# DC_SPS.net
KiCad netlist of a schematic drawn in Altium Designer
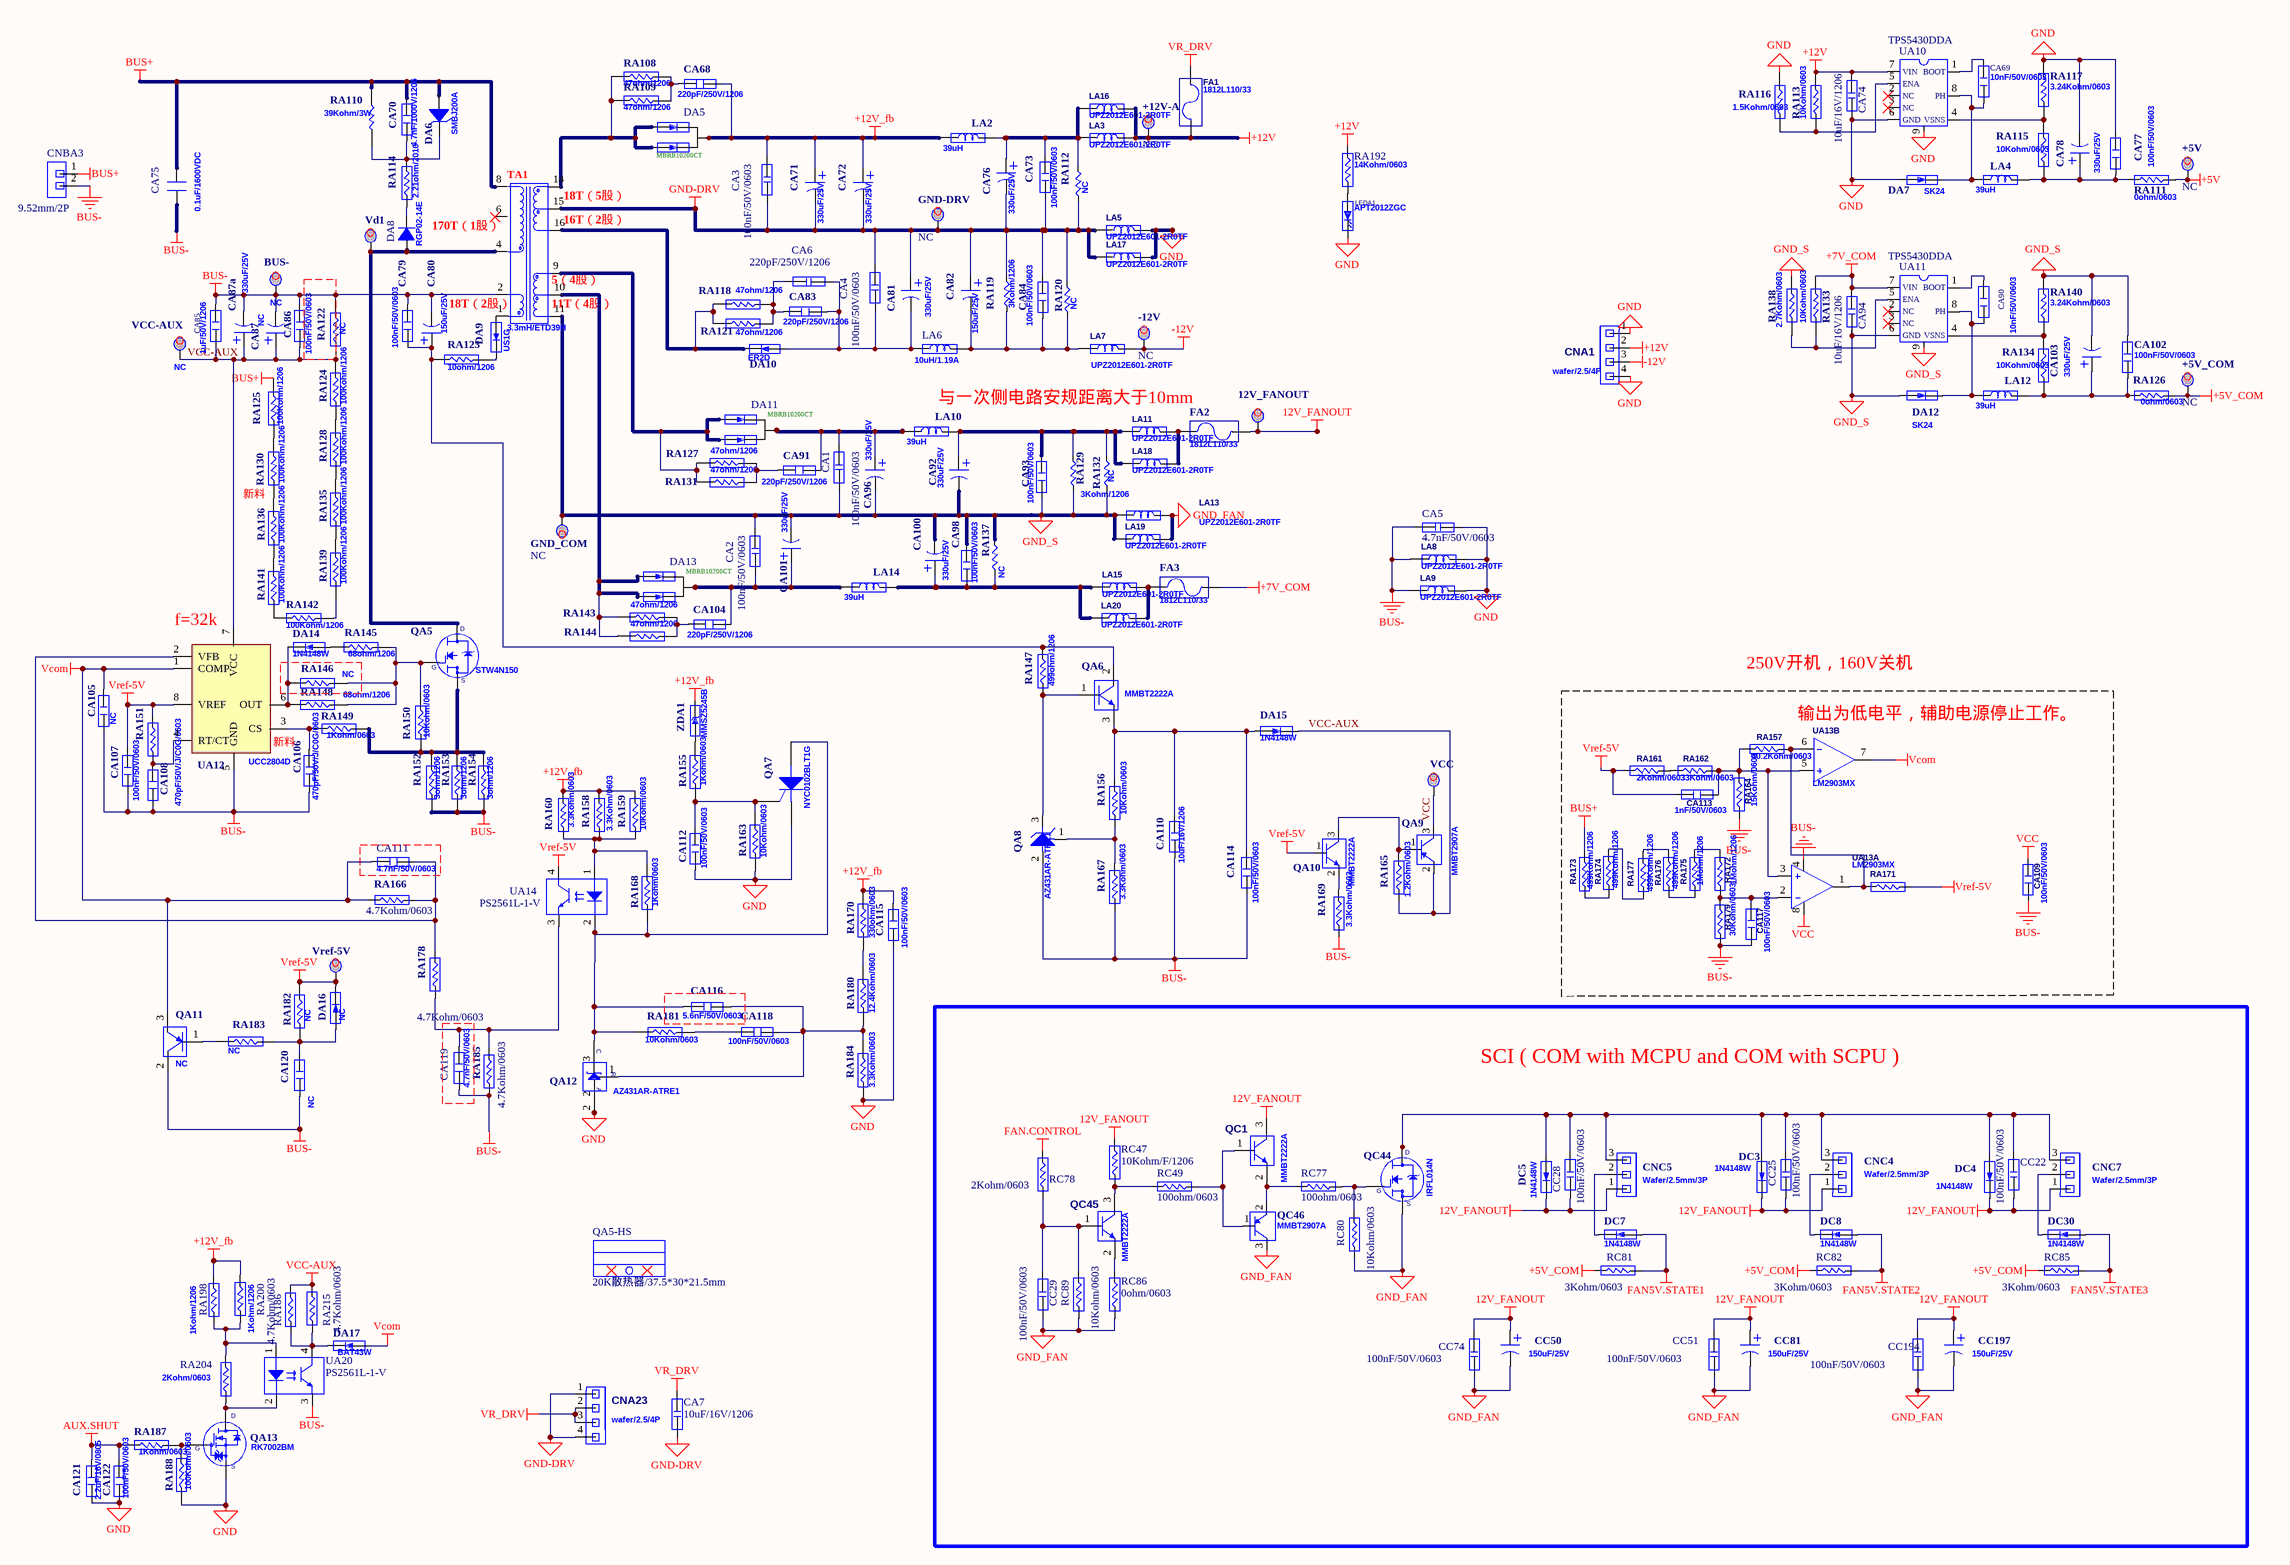
[diagram p0: DC SPS.SchDoc]

(export (version "E")
  (design (tool "Eeschema 10.0.6"))
  (components
    (comp (ref "+5V") (value "NC") (footprint "TEST-12") (libsource (lib "00") (part "17K TPD")))
    (comp (ref "+5V_COM") (value "NC") (footprint "TEST-12") (libsource (lib "00") (part "17K TPD")))
    (comp (ref "+12V-A") (value "NC") (footprint "TEST-12") (libsource (lib "00") (part "17K TPD")))
    (comp (ref "-12V") (value "NC") (footprint "TEST-12") (libsource (lib "00") (part "17K TPD")))
    (comp (ref "12V_FANOUT") (value "NC") (footprint "TEST-12") (libsource (lib "00") (part "17K TPD")))
    (comp (ref "BUS-") (value "NC") (footprint "TEST-12") (libsource (lib "00") (part "17K TPD")))
    (comp (ref "CA1")
      (value "100nF/50V/0603")
      (footprint "C0603SM")
      (description "100nF/50V/J/X7R/0603")
      (fields (field (name "Comment") "023-105220-0"))
      (libsource (lib "首航") (part "023-104320-0 C0603SM"))
    )
    (comp (ref "CA2")
      (value "100nF/50V/0603")
      (footprint "C0603SM")
      (description "100nF/50V/J/X7R/0603")
      (fields (field (name "Comment") "023-105220-0"))
      (libsource (lib "首航") (part "023-104320-0 C0603SM"))
    )
    (comp (ref "CA3")
      (value "100nF/50V/0603")
      (footprint "C0603SM")
      (description "100nF/50V/J/X7R/0603")
      (fields (field (name "Comment") "023-105220-0"))
      (libsource (lib "首航") (part "023-104320-0 C0603SM"))
    )
    (comp (ref "CA4")
      (value "100nF/50V/0603")
      (footprint "C0603SM")
      (description "100nF/50V/J/X7R/0603")
      (fields (field (name "Comment") "023-105220-0"))
      (libsource (lib "首航") (part "023-104320-0 C0603SM"))
    )
    (comp (ref "CA5")
      (value "4.7nF/50V/0603")
      (footprint "C0603SM")
      (description "4.7nF/50V/J/X7R/0603")
      (fields (field (name "Comment") "023-472220-0"))
      (libsource (lib "首航") (part "023-472220-0 C0603SM"))
    )
    (comp (ref "CA6")
      (value "220pF/250V/1206")
      (footprint "C1206SM")
      (description "220pF/250V/J/C0G/1206")
      (fields (field (name "Comment") "023-221250-0"))
      (libsource (lib "首航") (part "023-221250-0 C1206SM"))
    )
    (comp (ref "CA7")
      (value "10uF/16V/1206")
      (footprint "C1206SM")
      (description "10uF/16V/K/X7R/1206")
      (fields (field (name "Comment") "023-106350-0"))
      (libsource (lib "首航") (part "023-106350-0 C1206SM"))
    )
    (comp (ref "CA68")
      (value "220pF/250V/1206")
      (footprint "CC3216-1206")
      (description "220pF/250V/J/C0G/1206")
      (fields (field (name "Comment") "023-221250-0"))
      (libsource (lib "00") (part "C1206 SM"))
    )
    (comp (ref "CA69")
      (value "10nF/50V/0603")
      (footprint "CC1608-0603")
      (description "10nF/50V/J/X7R/0603")
      (fields (field (name "Comment") "023-103220-0"))
      (libsource (lib "CAP") (part "CC0603-103SM_J"))
    )
    (comp (ref "CA70")
      (value "4.7nF/1000V/1206")
      (footprint "CC3216-1206")
      (description "4.7nF/1000V/K/X7R/1206")
      (fields (field (name "Comment") "023-472350-0"))
      (libsource (lib "00") (part "17KC472/1KV"))
    )
    (comp (ref "CA71")
      (value "330uF/25V")
      (footprint "EC3.5/8.5")
      (description "330uF/25V/Φ8*15/4000H/EKY")
      (fields (field (name "Comment") "020-337100-0"))
      (libsource (lib "00") (part "C220UF/25V"))
    )
    (comp (ref "CA72")
      (value "330uF/25V")
      (footprint "EC3.5/8.5")
      (description "330uF/25V/Φ8*15/4000H/EKY")
      (fields (field (name "Comment") "020-337100-0"))
      (libsource (lib "00") (part "C220UF/25V"))
    )
    (comp (ref "CA73")
      (value "100nF/50V/0603")
      (footprint "CC1608-0603")
      (description "100nF/50V/J/X7R/0603")
      (fields (field (name "Comment") "023-105220-0"))
      (libsource (lib "00") (part "C0603 SM"))
    )
    (comp (ref "CA74")
      (value "10uF/16V/1206")
      (footprint "C1206SM")
      (description "10uF/16V/K/X7R/1206")
      (fields (field (name "Comment") "023-106350-0"))
      (libsource (lib "首航") (part "023-106350-0 C1206SM"))
    )
    (comp (ref "CA75")
      (value "0.1uF/1600VDC")
      (footprint "PC104/1600V-22.5")
      (description "0.1uF/1600VDC/±10%/P22.5/12*22*26.5")
      (fields (field (name "Comment") "022-104001-0"))
      (libsource (lib "CAP") (part "PC0.1uF/1600V"))
    )
    (comp (ref "CA76")
      (value "330uF/25V")
      (footprint "EC3.5/8.5")
      (description "330uF/25V/Φ8*15/4000H/EKY")
      (fields (field (name "Comment") "020-337100-0"))
      (libsource (lib "00") (part "C220UF/25V"))
    )
    (comp (ref "CA77")
      (value "100nF/50V/0603")
      (footprint "CC1608-0603")
      (description "100nF/50V/J/X7R/0603")
      (fields (field (name "Comment") "023-105220-0"))
      (libsource (lib "00") (part "C0603 SM"))
    )
    (comp (ref "CA78")
      (value "330uF/25V")
      (footprint "EC3.5/8.5")
      (description "330uF/25V/Φ8*15/4000H/EKY")
      (fields (field (name "Comment") "020-337100-0"))
      (libsource (lib "00") (part "C220UF/25V"))
    )
    (comp (ref "CA79")
      (value "100nF/50V/0603")
      (footprint "CC1608-0603")
      (description "100nF/50V/J/X7R/0603")
      (fields (field (name "Comment") "023-105220-0"))
      (libsource (lib "00") (part "C0603 SM"))
    )
    (comp (ref "CA80")
      (value "150uF/25V")
      (footprint "EC2.54/6.3")
      (description "150uF/25V/P2.5/Φ6.3*11/6000H")
      (fields (field (name "Comment") "020-157111-0"))
      (libsource (lib "00") (part "C100UF插件"))
    )
    (comp (ref "CA81")
      (value "330uF/25V")
      (footprint "EC3.5/8.5")
      (description "330uF/25V/Φ8*15/4000H/EKY")
      (fields (field (name "Comment") "020-337100-0"))
      (libsource (lib "00") (part "C220UF/25V"))
    )
    (comp (ref "CA82")
      (value "150uF/25V")
      (footprint "EC2.54/6.3")
      (description "150uF/25V/P2.5/Φ6.3*11/6000H")
      (fields (field (name "Comment") "020-157111-0"))
      (libsource (lib "00") (part "C100UF插件"))
    )
    (comp (ref "CA83")
      (value "220pF/250V/1206")
      (footprint "CC3216-1206")
      (description "220pF/250V/J/C0G/1206")
      (fields (field (name "Comment") "023-221250-0"))
      (libsource (lib "00") (part "C1206 SM"))
    )
    (comp (ref "CA84")
      (value "100nF/50V/0603")
      (footprint "CC1608-0603")
      (description "100nF/50V/J/X7R/0603")
      (fields (field (name "Comment") "023-105220-0"))
      (libsource (lib "00") (part "C0603 SM"))
    )
    (comp (ref "CA85")
      (value "1uF/50V/1206")
      (footprint "CC3216-1206")
      (description "1uF/50V/K/X7R/1206")
      (fields (field (name "Comment") "023-105250-0"))
      (libsource (lib "00") (part "C1206 SM"))
    )
    (comp (ref "CA86")
      (value "100nF/50V/0603")
      (footprint "CC1608-0603")
      (description "100nF/50V/J/X7R/0603")
      (fields (field (name "Comment") "023-105220-0"))
      (libsource (lib "00") (part "C0603 SM"))
    )
    (comp (ref "CA87") (value "NC") (footprint "EC2.54/6.3") (libsource (lib "00") (part "C100UF插件")))
    (comp (ref "CA87a")
      (value "330uF/25V")
      (footprint "EC3.5/8.5")
      (description "330uF/25V/Φ8*15/4000H/EKY")
      (fields (field (name "Comment") "020-337100-0"))
      (libsource (lib "00") (part "C220UF/25V"))
    )
    (comp (ref "CA90")
      (value "10nF/50V/0603")
      (footprint "CC1608-0603")
      (description "10nF/50V/J/X7R/0603")
      (fields (field (name "Comment") "023-103220-0"))
      (libsource (lib "CAP") (part "CC0603-103SM_J"))
    )
    (comp (ref "CA91")
      (value "220pF/250V/1206")
      (footprint "CC3216-1206")
      (description "220pF/250V/J/C0G/1206")
      (fields (field (name "Comment") "023-221250-0"))
      (libsource (lib "00") (part "C1206 SM"))
    )
    (comp (ref "CA92")
      (value "330uF/25V")
      (footprint "EC3.5/8.5")
      (description "330uF/25V/Φ8*15/4000H/EKY")
      (fields (field (name "Comment") "020-337100-0"))
      (libsource (lib "00") (part "C220UF/25V"))
    )
    (comp (ref "CA93")
      (value "100nF/50V/0603")
      (footprint "CC1608-0603")
      (description "100nF/50V/J/X7R/0603")
      (fields (field (name "Comment") "023-105220-0"))
      (libsource (lib "00") (part "C0603 SM"))
    )
    (comp (ref "CA94")
      (value "10uF/16V/1206")
      (footprint "C1206SM")
      (description "10uF/16V/K/X7R/1206")
      (fields (field (name "Comment") "023-106350-0"))
      (libsource (lib "首航") (part "023-106350-0 C1206SM"))
    )
    (comp (ref "CA96")
      (value "330uF/25V")
      (footprint "EC3.5/8.5")
      (description "330uF/25V/Φ8*15/4000H/EKY")
      (fields (field (name "Comment") "020-337100-0"))
      (libsource (lib "00") (part "C220UF/25V"))
    )
    (comp (ref "CA98")
      (value "100nF/50V/0603")
      (footprint "CC1608-0603")
      (description "100nF/50V/J/X7R/0603")
      (fields (field (name "Comment") "023-105220-0"))
      (libsource (lib "00") (part "C0603 SM"))
    )
    (comp (ref "CA100")
      (value "330uF/25V")
      (footprint "EC3.5/8.5")
      (description "330uF/25V/Φ8*15/4000H/EKY")
      (fields (field (name "Comment") "020-337100-0"))
      (libsource (lib "00") (part "C220UF/25V"))
    )
    (comp (ref "CA101")
      (value "330uF/25V")
      (footprint "EC3.5/8.5")
      (description "330uF/25V/Φ8*15/4000H/EKY")
      (fields (field (name "Comment") "020-337100-0"))
      (libsource (lib "00") (part "C220UF/25V"))
    )
    (comp (ref "CA102")
      (value "100nF/50V/0603")
      (footprint "CC1608-0603")
      (description "100nF/50V/J/X7R/0603")
      (fields (field (name "Comment") "023-105220-0"))
      (libsource (lib "00") (part "C0603 SM"))
    )
    (comp (ref "CA103")
      (value "330uF/25V")
      (footprint "EC3.5/8.5")
      (description "330uF/25V/Φ8*15/4000H/EKY")
      (fields (field (name "Comment") "020-337100-0"))
      (libsource (lib "00") (part "C220UF/25V"))
    )
    (comp (ref "CA104")
      (value "220pF/250V/1206")
      (footprint "CC3216-1206")
      (description "220pF/250V/J/C0G/1206")
      (fields (field (name "Comment") "023-221250-0"))
      (libsource (lib "00") (part "C1206 SM"))
    )
    (comp (ref "CA105") (value "NC") (footprint "CC1608-0603") (libsource (lib "00") (part "C0603 SM")))
    (comp (ref "CA106")
      (value "470pF/50V/J/C0G/0603")
      (footprint "CC1608-0603")
      (fields (field (name "Comment") "023-471220-0"))
      (libsource (lib "00") (part "C0603 SM"))
    )
    (comp (ref "CA107")
      (value "100nF/50V/0603")
      (footprint "CC1608-0603")
      (description "100nF/50V/J/X7R/0603")
      (fields (field (name "Comment") "023-105220-0"))
      (libsource (lib "") (part "C0603 SM_1"))
    )
    (comp (ref "CA108")
      (value "470pF/50V/J/C0G/0603")
      (footprint "CC1608-0603")
      (fields (field (name "Comment") "023-471220-0"))
      (libsource (lib "CAP") (part "CC0603-471SM"))
    )
    (comp (ref "CA109")
      (value "100nF/50V/0603")
      (footprint "CC1608-0603")
      (description "100nF/50V/J/X7R/0603")
      (fields (field (name "Comment") "023-105220-0"))
      (libsource (lib "CAP") (part "CC0603-104SM_J"))
    )
    (comp (ref "CA110")
      (value "10uF/16V/1206")
      (footprint "CC3216-1206")
      (description "10uF/16V/K/X7R/1206")
      (fields (field (name "Comment") "023-106350-0"))
      (libsource (lib "CAP") (part "CC1206-106/16VSM"))
    )
    (comp (ref "CA111")
      (value "4.7nF/50V/0603")
      (footprint "CC1608-0603")
      (description "4.7nF/50V/J/X7R/0603")
      (fields (field (name "Comment") "023-472220-0"))
      (libsource (lib "CAP") (part "CC0603-103SM"))
    )
    (comp (ref "CA112")
      (value "100nF/50V/0603")
      (footprint "CC1608-0603")
      (description "100nF/50V/J/X7R/0603")
      (fields (field (name "Comment") "023-105220-0"))
      (libsource (lib "00") (part "C0603 SM"))
    )
    (comp (ref "CA113")
      (value "1nF/50V/0603")
      (footprint "CC1608-0603")
      (description "1nF/50V/J/C0G/0603")
      (fields (field (name "Comment") "023-102220-0"))
      (libsource (lib "CAP") (part "CC0603-102SM"))
    )
    (comp (ref "CA114")
      (value "100nF/50V/0603")
      (footprint "CC1608-0603")
      (description "100nF/50V/J/X7R/0603")
      (fields (field (name "Comment") "023-105220-0"))
      (libsource (lib "00") (part "C0603 SM"))
    )
    (comp (ref "CA115")
      (value "100nF/50V/0603")
      (footprint "CC1608-0603")
      (description "100nF/50V/J/X7R/0603")
      (fields (field (name "Comment") "023-105220-0"))
      (libsource (lib "00") (part "C0603 SM"))
    )
    (comp (ref "CA116")
      (value "5.6nF/50V/0603")
      (footprint "CC1608-0603")
      (description "5.6nF/50V/K/0603")
      (fields (field (name "Comment") "023-562220-0"))
      (libsource (lib "") (part "C0603 SM_1"))
    )
    (comp (ref "CA117")
      (value "100nF/50V/0603")
      (footprint "CC1608-0603")
      (description "100nF/50V/J/X7R/0603")
      (fields (field (name "Comment") "023-105220-0"))
      (libsource (lib "CAP") (part "CC0603-104SM_J"))
    )
    (comp (ref "CA118")
      (value "100nF/50V/0603")
      (footprint "CC1608-0603")
      (description "100nF/50V/J/X7R/0603")
      (fields (field (name "Comment") "023-105220-0"))
      (libsource (lib "00") (part "C0603 SM"))
    )
    (comp (ref "CA119")
      (value "4.7nF/50V/0603")
      (footprint "CC1608-0603")
      (description "4.7nF/50V/J/X7R/0603")
      (fields (field (name "Comment") "023-472220-0"))
      (libsource (lib "CAP") (part "CC0603-103SM"))
    )
    (comp (ref "CA120") (value "NC") (footprint "CC1608-0603") (libsource (lib "00") (part "C0603 SM")))
    (comp (ref "CA121")
      (value "2.2uF/16V/0805")
      (footprint "CC2012-0805")
      (description "2.2uF/16V/K/X7R/0805")
      (fields (field (name "Comment") "023-225330-0"))
      (libsource (lib "CAP") (part "CC0805-225/16VSM"))
    )
    (comp (ref "CA122")
      (value "100nF/50V/0603")
      (footprint "CC1608-0603")
      (description "100nF/50V/J/X7R/0603")
      (fields (field (name "Comment") "023-105220-0"))
      (libsource (lib "00") (part "C0603 SM"))
    )
    (comp (ref "CC22")
      (value "100nF/50V/0603")
      (footprint "C0603SM")
      (description "100nF/50V/J/X7R/0603")
      (fields (field (name "Comment") "023-105220-0"))
      (libsource (lib "首航") (part "023-104320-0 C0603SM"))
    )
    (comp (ref "CC25")
      (value "100nF/50V/0603")
      (footprint "C0603SM")
      (description "100nF/50V/J/X7R/0603")
      (fields (field (name "Comment") "023-105220-0"))
      (libsource (lib "首航") (part "023-104320-0 C0603SM"))
    )
    (comp (ref "CC28")
      (value "100nF/50V/0603")
      (footprint "C0603SM")
      (description "100nF/50V/J/X7R/0603")
      (fields (field (name "Comment") "023-105220-0"))
      (libsource (lib "首航") (part "023-104320-0 C0603SM"))
    )
    (comp (ref "CC29")
      (value "100nF/50V/0603")
      (footprint "C0603SM")
      (description "100nF/50V/J/X7R/0603")
      (fields (field (name "Comment") "023-105220-0"))
      (libsource (lib "首航") (part "023-104320-0 C0603SM"))
    )
    (comp (ref "CC50")
      (value "150uF/25V")
      (footprint "EC2.54/6.3")
      (description "150uF/25V/P2.5/Φ6.3*11/6000H")
      (fields (field (name "Comment") "020-157111-0"))
      (libsource (lib "00") (part "C100UF插件"))
    )
    (comp (ref "CC51")
      (value "100nF/50V/0603")
      (footprint "C0603SM")
      (description "100nF/50V/J/X7R/0603")
      (fields (field (name "Comment") "023-105220-0"))
      (libsource (lib "首航") (part "023-104320-0 C0603SM"))
    )
    (comp (ref "CC74")
      (value "100nF/50V/0603")
      (footprint "C0603SM")
      (description "100nF/50V/J/X7R/0603")
      (fields (field (name "Comment") "023-105220-0"))
      (libsource (lib "首航") (part "023-104320-0 C0603SM"))
    )
    (comp (ref "CC81")
      (value "150uF/25V")
      (footprint "EC2.54/6.3")
      (description "150uF/25V/P2.5/Φ6.3*11/6000H")
      (fields (field (name "Comment") "020-157111-0"))
      (libsource (lib "00") (part "C100UF插件"))
    )
    (comp (ref "CC194")
      (value "100nF/50V/0603")
      (footprint "C0603SM")
      (description "100nF/50V/J/X7R/0603")
      (fields (field (name "Comment") "023-105220-0"))
      (libsource (lib "首航") (part "023-104320-0 C0603SM"))
    )
    (comp (ref "CC197")
      (value "150uF/25V")
      (footprint "EC2.54/6.3")
      (description "150uF/25V/P2.5/Φ6.3*11/6000H")
      (fields (field (name "Comment") "020-157111-0"))
      (libsource (lib "00") (part "C100UF插件"))
    )
    (comp (ref "CNA1")
      (value "wafer/2.5/4P")
      (footprint "CN2.5-4P")
      (description "Wafer/2.5 pitch/4 pin/182度/白胶/带卡勾")
      (fields (field (name "Comment") "110-252000-0"))
      (libsource (lib "00") (part "CN 25P04"))
    )
    (comp (ref "CNA23")
      (value "wafer/2.5/4P")
      (footprint "CN2.5-4P")
      (description "Wafer/2.5 pitch/4 pin/182度/白胶/带卡勾")
      (fields (field (name "Comment") "110-252000-0"))
      (libsource (lib "00") (part "CN 25P04"))
    )
    (comp (ref "CNBA3")
      (value "9.52mm/2P")
      (footprint "CN2P9.52")
      (description "接线端子台/9.52mm/2P")
      (fields (field (name "Comment") "110-309501-0"))
      (libsource (lib "zcp") (part "110-309500-0 CN2P9.52"))
    )
    (comp (ref "CNC4")
      (value "Wafer/2.5mm/3P")
      (footprint "CN2.5-3P")
      (description "Wafer/2.5 pitch/3 pin/181度/白胶/带卡勾")
      (fields (field (name "Comment") "110-251000-0"))
      (libsource (lib "00") (part "CN 25P03"))
    )
    (comp (ref "CNC5")
      (value "Wafer/2.5mm/3P")
      (footprint "CN2.5-3P")
      (description "Wafer/2.5 pitch/3 pin/181度/白胶/带卡勾")
      (fields (field (name "Comment") "110-251000-0"))
      (libsource (lib "00") (part "CN 25P03"))
    )
    (comp (ref "CNC7")
      (value "Wafer/2.5mm/3P")
      (footprint "CN2.5-3P")
      (description "Wafer/2.5 pitch/3 pin/181度/白胶/带卡勾")
      (fields (field (name "Comment") "110-251000-0"))
      (libsource (lib "00") (part "CN 25P03"))
    )
    (comp (ref "DA5")
      (value "MBRB10200CT")
      (footprint "D2PAK - 1")
      (description "10A/200V/D(2)PAK")
      (fields (field (name "Comment") "060-310030-0"))
      (libsource (lib "samilpower_Library-01") (part "D MBRB10200CT"))
    )
    (comp (ref "DA6")
      (value "SMBJ200A")
      (footprint "TVS-SMB")
      (description "200V/600W/DO-214AA")
      (fields (field (name "Comment") "083-100010-0"))
      (libsource (lib "00") (part "17KP6SMBJ170"))
    )
    (comp (ref "DA7")
      (value "SK24")
      (footprint "DO-SMB")
      (description "2A/40V/DO-214AA")
      (fields (field (name "Comment") "060-310020-0"))
      (libsource (lib "00") (part "D SK24"))
    )
    (comp (ref "DA8")
      (value "RGP02-14E")
      (footprint "DO-5.08/2.5")
      (description "0.5A/1400V/DO-41")
      (fields (field (name "Comment") "060-100000-0"))
      (libsource (lib "zhu-lib") (part "D RGP02-14E"))
    )
    (comp (ref "DA9")
      (value "US1G")
      (footprint "DO-SMA")
      (description "1A/400V/DO-214AC")
      (fields (field (name "Comment") "060-110010-0"))
      (libsource (lib "00") (part "17KUS1G"))
    )
    (comp (ref "DA10")
      (value "ER2D")
      (footprint "DO-SMA")
      (description "2A/200V/SMB")
      (fields (field (name "Comment") "060-110000-0"))
      (libsource (lib "00") (part "D MURA220T3"))
    )
    (comp (ref "DA11")
      (value "MBRB10200CT")
      (footprint "D2PAK - 1")
      (description "10A/200V/D(2)PAK")
      (fields (field (name "Comment") "060-310030-0"))
      (libsource (lib "samilpower_Library-01") (part "D MBRB10200CT"))
    )
    (comp (ref "DA12")
      (value "SK24")
      (footprint "DO-SMB")
      (description "2A/40V/DO-214AA")
      (fields (field (name "Comment") "060-310020-0"))
      (libsource (lib "00") (part "D SK24"))
    )
    (comp (ref "DA13")
      (value "MBRB10200CT")
      (footprint "D2PAK - 1")
      (description "10A/200V/D(2)PAK")
      (fields (field (name "Comment") "060-310030-0"))
      (libsource (lib "samilpower_Library-01") (part "D MBRB10200CT"))
    )
    (comp (ref "DA14")
      (value "1N4148W")
      (footprint "SOD-123")
      (description "0.15A/75V/SOD-123")
      (fields (field (name "Comment") "060-500010-0"))
      (libsource (lib "00") (part "D 1N4148W"))
    )
    (comp (ref "DA15")
      (value "1N4148W")
      (footprint "SOD-123")
      (description "0.15A/75V/SOD-123")
      (fields (field (name "Comment") "060-500010-0"))
      (libsource (lib "00") (part "D 1N4148W"))
    )
    (comp (ref "DA16") (value "NC") (footprint "SOD-123") (libsource (lib "00") (part "D 1N4148W")))
    (comp (ref "DA17")
      (value "BAT43W")
      (footprint "SOD-123")
      (description "0.2A/30V/SOD-123")
      (fields (field (name "Comment") "060-310000-0"))
      (libsource (lib "00") (part "D S123SM"))
    )
    (comp (ref "DC3")
      (value "1N4148W")
      (footprint "SOD-123")
      (description "0.15A/75V/SOD-123")
      (fields (field (name "Comment") "060-500010-0"))
      (libsource (lib "00") (part "D 1N4148W"))
    )
    (comp (ref "DC4")
      (value "1N4148W")
      (footprint "SOD-123")
      (description "0.15A/75V/SOD-123")
      (fields (field (name "Comment") "060-500010-0"))
      (libsource (lib "00") (part "D 1N4148W"))
    )
    (comp (ref "DC5")
      (value "1N4148W")
      (footprint "SOD-123")
      (description "0.15A/75V/SOD-123")
      (fields (field (name "Comment") "060-500010-0"))
      (libsource (lib "00") (part "D 1N4148W"))
    )
    (comp (ref "DC7")
      (value "1N4148W")
      (footprint "SOD-123")
      (description "0.15A/75V/SOD-123")
      (fields (field (name "Comment") "060-500010-0"))
      (libsource (lib "00") (part "D 1N4148W"))
    )
    (comp (ref "DC8")
      (value "1N4148W")
      (footprint "SOD-123")
      (description "0.15A/75V/SOD-123")
      (fields (field (name "Comment") "060-500010-0"))
      (libsource (lib "00") (part "D 1N4148W"))
    )
    (comp (ref "DC30")
      (value "1N4148W")
      (footprint "SOD-123")
      (description "0.15A/75V/SOD-123")
      (fields (field (name "Comment") "060-500010-0"))
      (libsource (lib "00") (part "D 1N4148W"))
    )
    (comp (ref "FA1")
      (value "1812L110/33")
      (footprint "17KFUSE1812L110-33")
      (description "1812L Series/1.1A/33V")
      (fields (field (name "Comment") "160-201000-0"))
      (libsource (lib "01") (part "FS 1812L110-33MR"))
    )
    (comp (ref "FA2")
      (value "1812L110/33")
      (footprint "17KFUSE1812L110-33")
      (description "1812L Series/1.1A/33V")
      (fields (field (name "Comment") "160-201000-0"))
      (libsource (lib "00") (part "17KFUSE1812L110-33"))
    )
    (comp (ref "FA3")
      (value "1812L110/33")
      (footprint "17KFUSE1812L110-33")
      (description "1812L Series/1.1A/33V")
      (fields (field (name "Comment") "160-201000-0"))
      (libsource (lib "00") (part "17KFUSE1812L110-33"))
    )
    (comp (ref "GND-DRV") (value "NC") (footprint "TEST-12") (libsource (lib "00") (part "17K TPD")))
    (comp (ref "GND_COM") (value "NC") (footprint "TEST-12") (libsource (lib "00") (part "17K TPD")))
    (comp (ref "LA2")
      (value "39uH")
      (footprint "L1110SM- 39UH")
      (description "39uH/DR10*5.4RB K38/RI10*3.4*8.2 K38")
      (fields (field (name "Comment") "040-390000-0"))
      (libsource (lib "00") (part "L10090SM"))
    )
    (comp (ref "LA3")
      (value "UPZ2012E601-2R0TF")
      (footprint "L2012-0805")
      (description "600ohm/2A/100MHz/0805")
      (fields (field (name "Comment") "080-200000-0"))
      (libsource (lib "linshi") (part "L-UPZ2012E601-2R0TF"))
    )
    (comp (ref "LA4")
      (value "39uH")
      (footprint "L1110SM- 39UH")
      (description "39uH/DR10*5.4RB K38/RI10*3.4*8.2 K38")
      (fields (field (name "Comment") "040-390000-0"))
      (libsource (lib "00") (part "L10090SM"))
    )
    (comp (ref "LA5")
      (value "UPZ2012E601-2R0TF")
      (footprint "L2012-0805")
      (description "600ohm/2A/100MHz/0805")
      (fields (field (name "Comment") "080-200000-0"))
      (libsource (lib "linshi") (part "L-UPZ2012E601-2R0TF"))
    )
    (comp (ref "LA6")
      (value "10uH/1.19A")
      (footprint "L4848SM")
      (description "10uH/1.19A/±30%/4.8*4.8*2.8mm")
      (fields (field (name "Comment") "040-109100-0"))
      (libsource (lib "00") (part "L7444043100SM"))
    )
    (comp (ref "LA7")
      (value "UPZ2012E601-2R0TF")
      (footprint "L2012-0805")
      (description "600ohm/2A/100MHz/0805")
      (fields (field (name "Comment") "080-200000-0"))
      (libsource (lib "linshi") (part "L-UPZ2012E601-2R0TF"))
    )
    (comp (ref "LA8")
      (value "UPZ2012E601-2R0TF")
      (footprint "L2012-0805")
      (description "600ohm/2A/100MHz/0805")
      (fields (field (name "Comment") "080-200000-0"))
      (libsource (lib "linshi") (part "L-UPZ2012E601-2R0TF"))
    )
    (comp (ref "LA9")
      (value "UPZ2012E601-2R0TF")
      (footprint "L2012-0805")
      (description "600ohm/2A/100MHz/0805")
      (fields (field (name "Comment") "080-200000-0"))
      (libsource (lib "linshi") (part "L-UPZ2012E601-2R0TF"))
    )
    (comp (ref "LA10")
      (value "39uH")
      (footprint "L1110SM- 39UH")
      (description "39uH/DR10*5.4RB K38/RI10*3.4*8.2 K38")
      (fields (field (name "Comment") "040-390000-0"))
      (libsource (lib "00") (part "L10090SM"))
    )
    (comp (ref "LA11")
      (value "UPZ2012E601-2R0TF")
      (footprint "L2012-0805")
      (description "600ohm/2A/100MHz/0805")
      (fields (field (name "Comment") "080-200000-0"))
      (libsource (lib "linshi") (part "L-UPZ2012E601-2R0TF"))
    )
    (comp (ref "LA12")
      (value "39uH")
      (footprint "L1110SM- 39UH")
      (description "39uH/DR10*5.4RB K38/RI10*3.4*8.2 K38")
      (fields (field (name "Comment") "040-390000-0"))
      (libsource (lib "00") (part "L10090SM"))
    )
    (comp (ref "LA13")
      (value "UPZ2012E601-2R0TF")
      (footprint "L2012-0805")
      (description "600ohm/2A/100MHz/0805")
      (fields (field (name "Comment") "080-200000-0"))
      (libsource (lib "linshi") (part "L-UPZ2012E601-2R0TF"))
    )
    (comp (ref "LA14")
      (value "39uH")
      (footprint "L1110SM- 39UH")
      (description "39uH/DR10*5.4RB K38/RI10*3.4*8.2 K38")
      (fields (field (name "Comment") "040-390000-0"))
      (libsource (lib "00") (part "L10090SM"))
    )
    (comp (ref "LA15")
      (value "UPZ2012E601-2R0TF")
      (footprint "L2012-0805")
      (description "600ohm/2A/100MHz/0805")
      (fields (field (name "Comment") "080-200000-0"))
      (libsource (lib "linshi") (part "L-UPZ2012E601-2R0TF"))
    )
    (comp (ref "LA16")
      (value "UPZ2012E601-2R0TF")
      (footprint "L2012-0805")
      (description "600ohm/2A/100MHz/0805")
      (fields (field (name "Comment") "080-200000-0"))
      (libsource (lib "linshi") (part "L-UPZ2012E601-2R0TF"))
    )
    (comp (ref "LA17")
      (value "UPZ2012E601-2R0TF")
      (footprint "L2012-0805")
      (description "600ohm/2A/100MHz/0805")
      (fields (field (name "Comment") "080-200000-0"))
      (libsource (lib "linshi") (part "L-UPZ2012E601-2R0TF"))
    )
    (comp (ref "LA18")
      (value "UPZ2012E601-2R0TF")
      (footprint "L2012-0805")
      (description "600ohm/2A/100MHz/0805")
      (fields (field (name "Comment") "080-200000-0"))
      (libsource (lib "linshi") (part "L-UPZ2012E601-2R0TF"))
    )
    (comp (ref "LA19")
      (value "UPZ2012E601-2R0TF")
      (footprint "L2012-0805")
      (description "600ohm/2A/100MHz/0805")
      (fields (field (name "Comment") "080-200000-0"))
      (libsource (lib "linshi") (part "L-UPZ2012E601-2R0TF"))
    )
    (comp (ref "LA20")
      (value "UPZ2012E601-2R0TF")
      (footprint "L2012-0805")
      (description "600ohm/2A/100MHz/0805")
      (fields (field (name "Comment") "080-200000-0"))
      (libsource (lib "linshi") (part "L-UPZ2012E601-2R0TF"))
    )
    (comp (ref "LEDA1")
      (value "APT2012ZGC")
      (footprint "LED2012-0805SM")
      (description "2.0*1.25*0.75mm/Green")
      (fields (field (name "Comment") "060-011000-0"))
      (libsource (lib "zhu-lib") (part "D LED0805_Green"))
    )
    (comp (ref "QA5")
      (value "STW4N150")
      (footprint "TO-247")
      (description "4A/1500V/TO-247")
      (fields (field (name "Comment") "063-000010-0"))
      (libsource (lib "00") (part "17KIRF740"))
    )
    (comp (ref "QA5-HS")
      (value "20K散热器/37.5*30*21.5mm")
      (footprint "HS30x10x37.5")
      (fields (field (name "Comment") "431-100000-0"))
      (libsource (lib "zcp") (part "431-100000-0 HS30x10x37.5"))
    )
    (comp (ref "QA6")
      (value "MMBT2222A")
      (footprint "SOT-23")
      (description "0.6A/40VDC/SOT-23")
      (fields (field (name "Comment") "061-010000-0"))
      (libsource (lib "01") (part "TR 2SC4672SM"))
    )
    (comp (ref "QA7")
      (value "NYC0102BLT1G")
      (footprint "SOT-23")
      (description "0.25A/200V/SOT-23")
      (fields (field (name "Comment") "062-000010-0"))
      (libsource (lib "Miscellaneous Devices") (part "SCR"))
    )
    (comp (ref "QA8")
      (value "AZ431AR-ATRE1")
      (footprint "SOT89N")
      (description "Shunt Regulators/SOT-89")
      (fields (field (name "Comment") "050-210020-0"))
      (libsource (lib "01") (part "IC TL431SM"))
    )
    (comp (ref "QA9")
      (value "MMBT2907A")
      (footprint "SOT-23")
      (description "0.6A/60VDC/SOT-23")
      (fields (field (name "Comment") "061-110000-0"))
      (libsource (lib "01") (part "TR 2907SM"))
    )
    (comp (ref "QA10")
      (value "MMBT2222A")
      (footprint "SOT-23")
      (description "0.6A/40VDC/SOT-23")
      (fields (field (name "Comment") "061-010000-0"))
      (libsource (lib "01") (part "TR 2222SM"))
    )
    (comp (ref "QA11") (value "NC") (footprint "SOT-23") (libsource (lib "01") (part "TR 2SA1213SM")))
    (comp (ref "QA12")
      (value "AZ431AR-ATRE1")
      (footprint "SOT89N")
      (description "Shunt Regulators/SOT-89")
      (fields (field (name "Comment") "050-210020-0"))
      (libsource (lib "00") (part "IC 431SM"))
    )
    (comp (ref "QA13")
      (value "RK7002BM")
      (footprint "SOT-23 - 1")
      (description "250mA/60V/SOT-23")
      (fields (field (name "Comment") "063-010010-0"))
      (libsource (lib "samilpower_Library-01") (part "MOS RK7002SM"))
    )
    (comp (ref "QC1")
      (value "MMBT2222A")
      (footprint "SOT-23")
      (description "0.6A/40VDC/SOT-23")
      (fields (field (name "Comment") "061-010000-0"))
      (libsource (lib "samilpower_Library-01") (part "TR 2222SM"))
    )
    (comp (ref "QC44")
      (value "IRFL014N")
      (footprint "SOT223")
      (description "1.9A/55V/SOT-223")
      (fields (field (name "Comment") "063-010000-0"))
      (libsource (lib "00") (part "17KIRFL014NTRPBF"))
    )
    (comp (ref "QC45")
      (value "MMBT2222A")
      (footprint "SOT-23")
      (description "0.6A/40VDC/SOT-23")
      (fields (field (name "Comment") "061-010000-0"))
      (libsource (lib "samilpower_Library-01") (part "TR 2222SM"))
    )
    (comp (ref "QC46")
      (value "MMBT2907A")
      (footprint "SOT-23")
      (description "0.6A/60VDC/SOT-23")
      (fields (field (name "Comment") "061-110000-0"))
      (libsource (lib "01") (part "TR 2907SM"))
    )
    (comp (ref "RA108")
      (value "47ohm/1206")
      (footprint "R3216-1206")
      (description "47ohm/1/4W/F/1206")
      (fields (field (name "Comment") "011-470050-0"))
      (libsource (lib "00") (part "R1206SM"))
    )
    (comp (ref "RA109")
      (value "47ohm/1206")
      (footprint "R3216-1206")
      (description "47ohm/1/4W/F/1206")
      (fields (field (name "Comment") "011-470050-0"))
      (libsource (lib "00") (part "R1206SM"))
    )
    (comp (ref "RA110")
      (value "39Kohm/3W")
      (footprint "R3WA-5.0-S")
      (description "39Kohm/3W/J/15.5*5")
      (fields (field (name "Comment") "013-390240-0"))
      (libsource (lib "ZHU") (part "RSS 3W 39K"))
    )
    (comp (ref "RA111")
      (value "0ohm/0603")
      (footprint "R1608-0603")
      (description "0ohm/1/10W/F/0603")
      (fields (field (name "Comment") "011-000020-0"))
      (libsource (lib "RES") (part "R0603SM-3K3"))
    )
    (comp (ref "RA112") (value "NC") (footprint "R3216-1206") (libsource (lib "RES") (part "R3W-7K5")))
    (comp (ref "RA113")
      (value "10Kohm/0603")
      (footprint "R1608-0603")
      (description "10Kohm/1/10W/F/0603")
      (fields (field (name "Comment") "011-103020-0"))
      (libsource (lib "00") (part "R0603SM"))
    )
    (comp (ref "RA114")
      (value "2.21ohm/2010")
      (footprint "R5025-2010")
      (description "2.21ohm/1/2W/F/2010")
      (fields (field (name "Comment") "011-227070-0"))
      (libsource (lib "RES") (part "R2010SM-221R"))
    )
    (comp (ref "RA115")
      (value "10Kohm/0603")
      (footprint "R1608-0603")
      (description "10Kohm/1/10W/F/0603")
      (fields (field (name "Comment") "011-103020-0"))
      (libsource (lib "00") (part "R0603SM"))
    )
    (comp (ref "RA116")
      (value "1.5Kohm/0603")
      (footprint "R1608-0603")
      (description "1.5Kohm/1/10W/F/0603")
      (fields (field (name "Comment") "011-152020-0"))
      (libsource (lib "00") (part "R0603SM"))
    )
    (comp (ref "RA117")
      (value "3.24Kohm/0603")
      (footprint "R1608-0603")
      (description "3.24Kohm/1/10W/F/0603")
      (fields (field (name "Comment") "011-322020-0"))
      (libsource (lib "00") (part "R0603SM"))
    )
    (comp (ref "RA118")
      (value "47ohm/1206")
      (footprint "R3216-1206")
      (description "47ohm/1/4W/F/1206")
      (fields (field (name "Comment") "011-470050-0"))
      (libsource (lib "00") (part "R1206SM"))
    )
    (comp (ref "RA119")
      (value "3Kohm/1206")
      (footprint "R3216-1206")
      (description "3Kohm/1/4W/F/1206")
      (fields (field (name "Comment") "011-302050-0"))
      (libsource (lib "RES") (part "R3W-7K5"))
    )
    (comp (ref "RA120") (value "NC") (footprint "R3216-1206") (libsource (lib "RES") (part "R3W-7K5")))
    (comp (ref "RA121")
      (value "47ohm/1206")
      (footprint "R3216-1206")
      (description "47ohm/1/4W/F/1206")
      (fields (field (name "Comment") "011-470050-0"))
      (libsource (lib "00") (part "R1206SM"))
    )
    (comp (ref "RA122") (value "NC") (footprint "R1608-0603") (libsource (lib "00") (part "R0603SM")))
    (comp (ref "RA123")
      (value "10ohm/1206")
      (footprint "R3216-1206")
      (description "10ohm/1/4W/F/1206")
      (fields (field (name "Comment") "011-100050-0"))
      (libsource (lib "00") (part "R1206SM"))
    )
    (comp (ref "RA124")
      (value "100Kohm/1206")
      (footprint "R3216-1206")
      (description "100Kohm/1/4W/F/1206")
      (fields (field (name "Comment") "011-104050-0"))
      (libsource (lib "00") (part "R1206SM"))
    )
    (comp (ref "RA125")
      (value "100Kohm/1206")
      (footprint "R3216-1206")
      (description "100Kohm/1/4W/F/1206")
      (fields (field (name "Comment") "011-104050-0"))
      (libsource (lib "00") (part "R1206SM"))
    )
    (comp (ref "RA126")
      (value "0ohm/0603")
      (footprint "R1608-0603")
      (description "0ohm/1/10W/F/0603")
      (fields (field (name "Comment") "011-000020-0"))
      (libsource (lib "RES") (part "R0603SM-3K3"))
    )
    (comp (ref "RA127")
      (value "47ohm/1206")
      (footprint "R3216-1206")
      (description "47ohm/1/4W/F/1206")
      (fields (field (name "Comment") "011-470050-0"))
      (libsource (lib "00") (part "R1206SM"))
    )
    (comp (ref "RA128")
      (value "100Kohm/1206")
      (footprint "R3216-1206")
      (description "100Kohm/1/4W/F/1206")
      (fields (field (name "Comment") "011-104050-0"))
      (libsource (lib "00") (part "R1206SM"))
    )
    (comp (ref "RA129")
      (value "3Kohm/1206")
      (footprint "R3216-1206")
      (description "3Kohm/1/4W/F/1206")
      (fields (field (name "Comment") "011-302050-0"))
      (libsource (lib "RES") (part "R3W-7K5"))
    )
    (comp (ref "RA130")
      (value "100Kohm/1206")
      (footprint "R3216-1206")
      (description "100Kohm/1/4W/F/1206")
      (fields (field (name "Comment") "011-104050-0"))
      (libsource (lib "00") (part "R1206SM"))
    )
    (comp (ref "RA131")
      (value "47ohm/1206")
      (footprint "R3216-1206")
      (description "47ohm/1/4W/F/1206")
      (fields (field (name "Comment") "011-470050-0"))
      (libsource (lib "00") (part "R1206SM"))
    )
    (comp (ref "RA132") (value "NC") (footprint "R3216-1206") (libsource (lib "RES") (part "R3W-7K5")))
    (comp (ref "RA133")
      (value "10Kohm/0603")
      (footprint "R1608-0603")
      (description "10Kohm/1/10W/F/0603")
      (fields (field (name "Comment") "011-103020-0"))
      (libsource (lib "00") (part "R0603SM"))
    )
    (comp (ref "RA134")
      (value "10Kohm/0603")
      (footprint "R1608-0603")
      (description "10Kohm/1/10W/F/0603")
      (fields (field (name "Comment") "011-103020-0"))
      (libsource (lib "00") (part "R0603SM"))
    )
    (comp (ref "RA135")
      (value "100Kohm/1206")
      (footprint "R3216-1206")
      (description "100Kohm/1/4W/F/1206")
      (fields (field (name "Comment") "011-104050-0"))
      (libsource (lib "00") (part "R1206SM"))
    )
    (comp (ref "RA136")
      (value "100Kohm/1206")
      (footprint "R3216-1206")
      (description "100Kohm/1/4W/F/1206")
      (fields (field (name "Comment") "011-104050-0"))
      (libsource (lib "00") (part "R1206SM"))
    )
    (comp (ref "RA137") (value "NC") (footprint "R3216-1206") (libsource (lib "RES") (part "R3W-7K5")))
    (comp (ref "RA138")
      (value "2.7Kohm/0603")
      (footprint "R1608-0603")
      (description "2.7Kohm/1/10W/F/0603")
      (fields (field (name "Comment") "011-272020-0"))
      (libsource (lib "00") (part "R0603SM"))
    )
    (comp (ref "RA139")
      (value "100Kohm/1206")
      (footprint "R3216-1206")
      (description "100Kohm/1/4W/F/1206")
      (fields (field (name "Comment") "011-104050-0"))
      (libsource (lib "00") (part "R1206SM"))
    )
    (comp (ref "RA140")
      (value "3.24Kohm/0603")
      (footprint "R1608-0603")
      (description "3.24Kohm/1/10W/F/0603")
      (fields (field (name "Comment") "011-322020-0"))
      (libsource (lib "00") (part "R0603SM"))
    )
    (comp (ref "RA141")
      (value "100Kohm/1206")
      (footprint "R3216-1206")
      (description "100Kohm/1/4W/F/1206")
      (fields (field (name "Comment") "011-104050-0"))
      (libsource (lib "00") (part "R1206SM"))
    )
    (comp (ref "RA142")
      (value "100Kohm/1206")
      (footprint "R3216-1206")
      (description "100Kohm/1/4W/F/1206")
      (fields (field (name "Comment") "011-104050-0"))
      (libsource (lib "00") (part "R1206SM"))
    )
    (comp (ref "RA143")
      (value "47ohm/1206")
      (footprint "R3216-1206")
      (description "47ohm/1/4W/F/1206")
      (fields (field (name "Comment") "011-470050-0"))
      (libsource (lib "00") (part "R1206SM"))
    )
    (comp (ref "RA144")
      (value "47ohm/1206")
      (footprint "R3216-1206")
      (description "47ohm/1/4W/F/1206")
      (fields (field (name "Comment") "011-470050-0"))
      (libsource (lib "00") (part "R1206SM"))
    )
    (comp (ref "RA145")
      (value "68ohm/1206")
      (footprint "R3216-1206")
      (description "68ohm/1/4W/F/1206")
      (fields (field (name "Comment") "011-680050-0"))
      (libsource (lib "00") (part "R1206SM"))
    )
    (comp (ref "RA146") (value "NC") (footprint "R3216-1206") (libsource (lib "00") (part "R1206SM")))
    (comp (ref "RA147")
      (value "499ohm/1206")
      (footprint "R3216-1206")
      (description "499ohm/1/4W/F/1206")
      (fields (field (name "Comment") "011-491050-0"))
      (libsource (lib "RES") (part "R1206SM-499R"))
    )
    (comp (ref "RA148")
      (value "68ohm/1206")
      (footprint "R3216-1206")
      (description "68ohm/1/4W/F/1206")
      (fields (field (name "Comment") "011-680050-0"))
      (libsource (lib "00") (part "R1206SM"))
    )
    (comp (ref "RA149")
      (value "1Kohm/0603")
      (footprint "R1608-0603")
      (description "1Kohm/1/10W/F/0603")
      (fields (field (name "Comment") "011-102020-0"))
      (libsource (lib "00") (part "R0603SM"))
    )
    (comp (ref "RA150")
      (value "10Kohm/0603")
      (footprint "R1608-0603")
      (description "10Kohm/1/10W/F/0603")
      (fields (field (name "Comment") "011-103020-0"))
      (libsource (lib "00") (part "R0603SM"))
    )
    (comp (ref "RA151")
      (value "011-493020-0")
      (footprint "R1608-0603")
      (description "49.9Kohm/1/10W/F/0603")
      (libsource (lib "RES") (part "R0603SM-49K9"))
    )
    (comp (ref "RA152")
      (value "3ohm/1206")
      (footprint "R3216-1206")
      (description "3ohm/1/4W/F/1206")
      (fields (field (name "Comment") "011-307050-0"))
      (libsource (lib "00") (part "R1206SM"))
    )
    (comp (ref "RA153")
      (value "3ohm/1206")
      (footprint "R3216-1206")
      (description "3ohm/1/4W/F/1206")
      (fields (field (name "Comment") "011-307050-0"))
      (libsource (lib "00") (part "R1206SM"))
    )
    (comp (ref "RA154")
      (value "3ohm/1206")
      (footprint "R3216-1206")
      (description "3ohm/1/4W/F/1206")
      (fields (field (name "Comment") "011-307050-0"))
      (libsource (lib "00") (part "R1206SM"))
    )
    (comp (ref "RA155")
      (value "1Kohm/0603")
      (footprint "R1608-0603")
      (description "1Kohm/1/10W/F/0603")
      (fields (field (name "Comment") "011-102020-0"))
      (libsource (lib "00") (part "R0603SM"))
    )
    (comp (ref "RA156")
      (value "10Kohm/0603")
      (footprint "R1608-0603")
      (description "10Kohm/1/10W/F/0603")
      (fields (field (name "Comment") "011-103020-0"))
      (libsource (lib "RES") (part "R0603SM-10K"))
    )
    (comp (ref "RA157")
      (value "40.2Kohm/0603")
      (footprint "R1608-0603")
      (description "40.2Kohm/1/10W/F/0603")
      (fields (field (name "Comment") "011-403020-0"))
      (libsource (lib "RES") (part "R0603SM-100K"))
    )
    (comp (ref "RA158")
      (value "3.3Kohm/0603")
      (footprint "R1608-0603")
      (description "3.3Kohm/1/10W/F/0603")
      (fields (field (name "Comment") "011-332020-0"))
      (libsource (lib "RES") (part "R0603SM-3K3"))
    )
    (comp (ref "RA159")
      (value "10Kohm/0603")
      (footprint "R1608-0603")
      (description "10Kohm/1/10W/F/0603")
      (fields (field (name "Comment") "011-103020-0"))
      (libsource (lib "RES") (part "R0603SM-3K3"))
    )
    (comp (ref "RA160")
      (value "3.3Kohm/0603")
      (footprint "R1608-0603")
      (description "3.3Kohm/1/10W/F/0603")
      (fields (field (name "Comment") "011-332020-0"))
      (libsource (lib "RES") (part "R0603SM-3K3"))
    )
    (comp (ref "RA161")
      (value "2Kohm/0603")
      (footprint "R1608-0603")
      (description "2Kohm/1/10W/F/0603")
      (fields (field (name "Comment") "011-202020-0"))
      (libsource (lib "RES") (part "R0603SM-30K"))
    )
    (comp (ref "RA162")
      (value "33Kohm/0603")
      (footprint "R1608-0603")
      (description "33Kohm/1/10W/F/0603")
      (fields (field (name "Comment") "011-333020-0"))
      (libsource (lib "RES") (part "R0603SM-30K"))
    )
    (comp (ref "RA163")
      (value "10Kohm/0603")
      (footprint "R1608-0603")
      (description "10Kohm/1/10W/F/0603")
      (fields (field (name "Comment") "011-103020-0"))
      (libsource (lib "00") (part "R0603SM"))
    )
    (comp (ref "RA164")
      (value "15Kohm/0603")
      (footprint "R1608-0603")
      (description "15Kohm/1/10W/F/0603")
      (fields (field (name "Comment") "011-153020-0"))
      (libsource (lib "RES") (part "R0603SM-15K"))
    )
    (comp (ref "RA165")
      (value "1.2Kohm/0603")
      (footprint "R1608-0603")
      (description "1.2Kohm/1/10W/F/0603")
      (fields (field (name "Comment") "011-122020-0"))
      (libsource (lib "RES") (part "R0603SM-1K2"))
    )
    (comp (ref "RA166")
      (value "4.7Kohm/0603")
      (footprint "R1608-0603")
      (description "4.7Kohm/1/10W/F/0603")
      (fields (field (name "Comment") "011-472020-0"))
      (libsource (lib "RES") (part "R0603SM-4K7"))
    )
    (comp (ref "RA167")
      (value "3.3Kohm/0603")
      (footprint "R1608-0603")
      (description "3.3Kohm/1/10W/F/0603")
      (fields (field (name "Comment") "011-332020-0"))
      (libsource (lib "RES") (part "R0603SM-3K3"))
    )
    (comp (ref "RA168")
      (value "1Kohm/0603")
      (footprint "R1608-0603")
      (description "1Kohm/1/10W/F/0603")
      (fields (field (name "Comment") "011-102020-0"))
      (libsource (lib "00") (part "R0603SM"))
    )
    (comp (ref "RA169")
      (value "3.3Kohm/0603")
      (footprint "R1608-0603")
      (description "3.3Kohm/1/10W/F/0603")
      (fields (field (name "Comment") "011-332020-0"))
      (libsource (lib "RES") (part "R0603SM-3K3"))
    )
    (comp (ref "RA170")
      (value "330ohm/0603")
      (footprint "R1608-0603")
      (description "330ohm/1/10W/F/0603")
      (fields (field (name "Comment") "011-331020-0"))
      (libsource (lib "00") (part "R0603SM"))
    )
    (comp (ref "RA171")
      (value "011-493020-0")
      (footprint "R1608-0603")
      (description "49.9Kohm/1/10W/F/0603")
      (libsource (lib "samilpower_Library-01") (part "R0603SM-49K9"))
    )
    (comp (ref "RA172")
      (value "1Mohm/1206")
      (footprint "R3216-1206")
      (description "1Mohm/1/4W/F/1206")
      (fields (field (name "Comment") "011-106050-0"))
      (libsource (lib "RES") (part "R1206SM-1M"))
    )
    (comp (ref "RA173")
      (value "499Kohm/1206")
      (footprint "R3216-1206")
      (description "499Kohm/1/4W/F/1206")
      (fields (field (name "Comment") "011-494050-0"))
      (libsource (lib "RES") (part "R1206SM-1M"))
    )
    (comp (ref "RA174")
      (value "499Kohm/1206")
      (footprint "R3216-1206")
      (description "499Kohm/1/4W/F/1206")
      (fields (field (name "Comment") "011-494050-0"))
      (libsource (lib "RES") (part "R1206SM-1M"))
    )
    (comp (ref "RA175")
      (value "1Mohm/1206")
      (footprint "R3216-1206")
      (description "1Mohm/1/4W/F/1206")
      (fields (field (name "Comment") "011-106050-0"))
      (libsource (lib "RES") (part "R1206SM-1M"))
    )
    (comp (ref "RA176")
      (value "499Kohm/1206")
      (footprint "R3216-1206")
      (description "499Kohm/1/4W/F/1206")
      (fields (field (name "Comment") "011-494050-0"))
      (libsource (lib "RES") (part "R1206SM-1M"))
    )
    (comp (ref "RA177")
      (value "499Kohm/1206")
      (footprint "R3216-1206")
      (description "499Kohm/1/4W/F/1206")
      (fields (field (name "Comment") "011-494050-0"))
      (libsource (lib "RES") (part "R1206SM-1M"))
    )
    (comp (ref "RA178")
      (value "4.7Kohm/0603")
      (footprint "R1608-0603")
      (description "4.7Kohm/1/10W/F/0603")
      (fields (field (name "Comment") "011-472020-0"))
      (libsource (lib "RES") (part "R0603SM-4K7"))
    )
    (comp (ref "RA179")
      (value "30Kohm/0603")
      (footprint "R1608-0603")
      (description "30Kohm/1/10W/F/0603")
      (fields (field (name "Comment") "011-303020-0"))
      (libsource (lib "RES") (part "R0603SM-30K"))
    )
    (comp (ref "RA180")
      (value "12.4Kohm/0603")
      (footprint "R1608-0603")
      (description "12.4Kohm/1/10W/F/0603")
      (fields (field (name "Comment") "011-123020-0"))
      (libsource (lib "00") (part "R0603SM"))
    )
    (comp (ref "RA181")
      (value "10Kohm/0603")
      (footprint "R1608-0603")
      (description "10Kohm/1/10W/F/0603")
      (fields (field (name "Comment") "011-103020-0"))
      (libsource (lib "00") (part "R0603SM"))
    )
    (comp (ref "RA182") (value "NC") (footprint "R1608-0603") (libsource (lib "00") (part "R0603SM")))
    (comp (ref "RA183") (value "NC") (footprint "R1608-0603") (libsource (lib "00") (part "R0603SM")))
    (comp (ref "RA184")
      (value "3.3Kohm/0603")
      (footprint "R1608-0603")
      (description "3.3Kohm/1/10W/F/0603")
      (fields (field (name "Comment") "011-332020-0"))
      (libsource (lib "00") (part "R0603SM"))
    )
    (comp (ref "RA185")
      (value "4.7Kohm/0603")
      (footprint "R1608-0603")
      (description "4.7Kohm/1/10W/F/0603")
      (fields (field (name "Comment") "011-472020-0"))
      (libsource (lib "RES") (part "R0603SM-4K7"))
    )
    (comp (ref "RA186")
      (value "4.7Kohm/0603")
      (footprint "R1608-0603")
      (description "4.7Kohm/1/10W/F/0603")
      (fields (field (name "Comment") "011-472020-0"))
      (libsource (lib "RES") (part "R0603SM-2K"))
    )
    (comp (ref "RA187")
      (value "1Kohm/0603")
      (footprint "R1608-0603")
      (description "1Kohm/1/10W/F/0603")
      (fields (field (name "Comment") "011-102020-0"))
      (libsource (lib "00") (part "R0603SM"))
    )
    (comp (ref "RA188")
      (value "100Kohm/0603")
      (footprint "R1608-0603")
      (description "100Kohm/1/10W/F/0603")
      (fields (field (name "Comment") "011-104020-0"))
      (libsource (lib "00") (part "R0603SM"))
    )
    (comp (ref "RA192")
      (value "14Kohm/0603")
      (footprint "R1608-0603")
      (description "14Kohm/1/10W/F/0603")
      (fields (field (name "Comment") "011-143020-0"))
      (libsource (lib "RES") (part "R0603SM-14K"))
    )
    (comp (ref "RA198")
      (value "1Kohm/1206")
      (footprint "R3216-1206")
      (description "1Kohm/1/4W/F/1206")
      (fields (field (name "Comment") "011-102050-0"))
      (libsource (lib "RES") (part "R1206SM-100R"))
    )
    (comp (ref "RA200")
      (value "1Kohm/1206")
      (footprint "R3216-1206")
      (description "1Kohm/1/4W/F/1206")
      (fields (field (name "Comment") "011-102050-0"))
      (libsource (lib "RES") (part "R1206SM-100R"))
    )
    (comp (ref "RA204")
      (value "2Kohm/0603")
      (footprint "R1608-0603")
      (description "2Kohm/1/10W/F/0603")
      (fields (field (name "Comment") "011-202020-0"))
      (libsource (lib "RES") (part "R0603SM-2K"))
    )
    (comp (ref "RA215")
      (value "4.7Kohm/0603")
      (footprint "R1608-0603")
      (description "4.7Kohm/1/10W/F/0603")
      (fields (field (name "Comment") "011-472020-0"))
      (libsource (lib "RES") (part "R0603SM-2K"))
    )
    (comp (ref "RC47")
      (value "10Kohm/F/1206")
      (footprint "R1206SM")
      (description "10Kohm/1/4W/F/1206")
      (fields (field (name "Comment") "011-103050-0"))
      (libsource (lib "首航") (part "011-103050-0 R1206SM"))
    )
    (comp (ref "RC49")
      (value "100ohm/0603")
      (footprint "R0603SM")
      (description "100ohm/1/10W/F/0603")
      (fields (field (name "Comment") "011-101020-0"))
      (libsource (lib "首航") (part "011-101020-0 R0603SM"))
    )
    (comp (ref "RC77")
      (value "100ohm/0603")
      (footprint "R0603SM")
      (description "100ohm/1/10W/F/0603")
      (fields (field (name "Comment") "011-101020-0"))
      (libsource (lib "首航") (part "011-101020-0 R0603SM"))
    )
    (comp (ref "RC78")
      (value "2Kohm/0603")
      (footprint "R0603SM")
      (description "2Kohm/1/10W/F/0603")
      (fields (field (name "Comment") "011-202020-0"))
      (libsource (lib "首航") (part "011-202020-0 R0603SM"))
    )
    (comp (ref "RC80")
      (value "10Kohm/0603")
      (footprint "R0603SM")
      (description "10Kohm/1/10W/F/0603")
      (fields (field (name "Comment") "011-103020-0"))
      (libsource (lib "首航") (part "011-103020-0 R0603SM"))
    )
    (comp (ref "RC81")
      (value "3Kohm/0603")
      (footprint "R0603SM")
      (description "3Kohm/1/10W/F/0603")
      (fields (field (name "Comment") "011-302020-0"))
      (libsource (lib "首航") (part "011-302020-0 R0603SM"))
    )
    (comp (ref "RC82")
      (value "3Kohm/0603")
      (footprint "R0603SM")
      (description "3Kohm/1/10W/F/0603")
      (fields (field (name "Comment") "011-302020-0"))
      (libsource (lib "首航") (part "011-302020-0 R0603SM"))
    )
    (comp (ref "RC85")
      (value "3Kohm/0603")
      (footprint "R0603SM")
      (description "3Kohm/1/10W/F/0603")
      (fields (field (name "Comment") "011-302020-0"))
      (libsource (lib "首航") (part "011-302020-0 R0603SM"))
    )
    (comp (ref "RC86")
      (value "0ohm/0603")
      (footprint "R0603SM")
      (description "0ohm/1/10W/F/0603")
      (fields (field (name "Comment") "011-000020-0"))
      (libsource (lib "首航") (part "011-000020-0 R0603SM"))
    )
    (comp (ref "RC89")
      (value "10Kohm/0603")
      (footprint "R0603SM")
      (description "10Kohm/1/10W/F/0603")
      (fields (field (name "Comment") "011-103020-0"))
      (libsource (lib "首航") (part "011-103020-0 R0603SM"))
    )
    (comp (ref "TA1")
      (value "3.3mH/ETD39H")
      (footprint "EC39(8+8P)-1")
      (description "3.3mH/ETD39H/PC40/卧式/KB1892-20156")
      (fields (field (name "Comment") "030-001000-0"))
      (libsource (lib "zcp") (part "ETD29 -1"))
    )
    (comp (ref "UA10")
      (value "TPS5430DDA")
      (footprint "SO8-5X4-PD")
      (description "Converter/SO-8")
      (fields (field (name "Comment") "050-210030-0"))
      (libsource (lib "首航") (part "050-210030-0 SO8-5X4-PD"))
    )
    (comp (ref "UA11")
      (value "TPS5430DDA")
      (footprint "SO8-5X4-PD")
      (description "Converter/SO-8")
      (fields (field (name "Comment") "050-210030-0"))
      (libsource (lib "首航") (part "050-210030-0 SO8-5X4-PD"))
    )
    (comp (ref "UA12")
      (value "UCC2804D")
      (footprint "SO8")
      (description "Current-Mode PWM/SOIC-8")
      (fields (field (name "Comment") "050-410010-0"))
      (libsource (lib "00") (part "17KUC2845D8"))
    )
    (comp (ref "UA13")
      (value "LM2903MX")
      (footprint "SO8")
      (description "Voltage Dual Comparator/SOIC-8")
      (fields (field (name "Comment") "050-610040-0"))
      (libsource (lib "01") (part "IC LM2903IM-SM"))
    )
    (comp (ref "UA14")
      (value "PS2561L-1-V")
      (footprint "LTV816SB-V")
      (description "Optocoupler/SO-4")
      (fields (field (name "Comment") "050-010000-0"))
      (libsource (lib "新增元件") (part "050-011000-0 LTV816SB-V"))
    )
    (comp (ref "UA20")
      (value "PS2561L-1-V")
      (footprint "LTV816SB-V")
      (description "Optocoupler/SO-4")
      (fields (field (name "Comment") "050-010000-0"))
      (libsource (lib "新增元件") (part "050-011000-0 LTV816SB-V"))
    )
    (comp (ref "VCC") (value "NC") (footprint "TEST-12") (libsource (lib "00") (part "17K TPD")))
    (comp (ref "VCC-AUX") (value "NC") (footprint "TEST-12") (libsource (lib "00") (part "17K TPD")))
    (comp (ref "Vd1") (value "NC") (footprint "TEST-12") (libsource (lib "00") (part "17K TPD")))
    (comp (ref "Vref-5V") (value "NC") (footprint "TEST-12") (libsource (lib "00") (part "17K TPD")))
    (comp (ref "ZDA1")
      (value "MMSZ5245B")
      (footprint "SOD-123")
      (description "0.5W/15V/SOD-123")
      (fields (field (name "Comment") "060-210010-0"))
      (libsource (lib "samilpower_Library-01") (part "DZ MMSZ18VSM"))
    )
  )
  (nets
    (net (code "1") (name "+5V") (class "Default")
      (node (ref "+5V") (pin "1") (pinfunction "1_1") (pintype "passive"))
      (node (ref "RA111") (pin "1") (pinfunction "1_1") (pintype "passive"))
    )
    (net (code "2") (name "+5V_COM") (class "Default")
      (node (ref "+5V_COM") (pin "1") (pinfunction "1_1") (pintype "passive"))
      (node (ref "RA126") (pin "1") (pinfunction "1_1") (pintype "passive"))
      (node (ref "RC81") (pin "1") (pinfunction "1_1") (pintype "passive"))
      (node (ref "RC82") (pin "1") (pinfunction "1_1") (pintype "passive"))
      (node (ref "RC85") (pin "1") (pinfunction "1_1") (pintype "passive"))
    )
    (net (code "3") (name "+7V_COM") (class "Default")
      (node (ref "CA94") (pin "2") (pinfunction "2_2") (pintype "passive"))
      (node (ref "FA3") (pin "1") (pinfunction "1_1") (pintype "passive"))
      (node (ref "RA133") (pin "1") (pinfunction "1_1") (pintype "passive"))
      (node (ref "UA11") (pin "7") (pinfunction "VIN_7") (pintype "passive"))
    )
    (net (code "4") (name "+12V") (class "Default")
      (node (ref "+12V-A") (pin "1") (pinfunction "1_1") (pintype "passive"))
      (node (ref "CA74") (pin "2") (pinfunction "2_2") (pintype "passive"))
      (node (ref "CNA1") (pin "2") (pinfunction "2_2") (pintype "passive"))
      (node (ref "FA1") (pin "2") (pinfunction "2_2") (pintype "passive"))
      (node (ref "LA16") (pin "2") (pinfunction "2_2") (pintype "passive"))
      (node (ref "LA3") (pin "2") (pinfunction "2_2") (pintype "passive"))
      (node (ref "RA113") (pin "1") (pinfunction "1_1") (pintype "passive"))
      (node (ref "RA192") (pin "2") (pinfunction "2_2") (pintype "passive"))
      (node (ref "UA10") (pin "7") (pinfunction "VIN_7") (pintype "passive"))
    )
    (net (code "5") (name "+12V_fb") (class "Default")
      (node (ref "CA115") (pin "2") (pinfunction "2_2") (pintype "passive"))
      (node (ref "CA3") (pin "2") (pinfunction "2_2") (pintype "passive"))
      (node (ref "CA68") (pin "2") (pinfunction "2_2") (pintype "passive"))
      (node (ref "CA71") (pin "1") (pinfunction "1_1") (pintype "passive"))
      (node (ref "CA72") (pin "1") (pinfunction "1_1") (pintype "passive"))
      (node (ref "DA5") (pin "2") (pinfunction "2_2") (pintype "passive"))
      (node (ref "DA5") (pin "4") (pinfunction "4_4") (pintype "passive"))
      (node (ref "LA2") (pin "1") (pinfunction "1_1") (pintype "passive"))
      (node (ref "RA158") (pin "2") (pinfunction "2_2") (pintype "passive"))
      (node (ref "RA159") (pin "2") (pinfunction "2_2") (pintype "passive"))
      (node (ref "RA160") (pin "2") (pinfunction "2_2") (pintype "passive"))
      (node (ref "RA170") (pin "2") (pinfunction "2_2") (pintype "passive"))
      (node (ref "RA198") (pin "2") (pinfunction "2_2") (pintype "passive"))
      (node (ref "RA200") (pin "2") (pinfunction "2_2") (pintype "passive"))
      (node (ref "ZDA1") (pin "2") (pinfunction "2_2") (pintype "passive"))
    )
    (net (code "6") (name "-12V") (class "Default")
      (node (ref "-12V") (pin "1") (pinfunction "1_1") (pintype "passive"))
      (node (ref "CNA1") (pin "3") (pinfunction "3_3") (pintype "passive"))
      (node (ref "LA7") (pin "2") (pinfunction "2_2") (pintype "passive"))
    )
    (net (code "7") (name "12V_FANOUT") (class "Default")
      (node (ref "12V_FANOUT") (pin "1") (pinfunction "1_1") (pintype "passive"))
      (node (ref "CC194") (pin "2") (pinfunction "2_2") (pintype "passive"))
      (node (ref "CC197") (pin "1") (pinfunction "1_1") (pintype "passive"))
      (node (ref "CC22") (pin "1") (pinfunction "1_1") (pintype "passive"))
      (node (ref "CC25") (pin "1") (pinfunction "1_1") (pintype "passive"))
      (node (ref "CC28") (pin "1") (pinfunction "1_1") (pintype "passive"))
      (node (ref "CC50") (pin "1") (pinfunction "1_1") (pintype "passive"))
      (node (ref "CC51") (pin "2") (pinfunction "2_2") (pintype "passive"))
      (node (ref "CC74") (pin "2") (pinfunction "2_2") (pintype "passive"))
      (node (ref "CC81") (pin "1") (pinfunction "1_1") (pintype "passive"))
      (node (ref "CNC4") (pin "1") (pinfunction "1_1") (pintype "passive"))
      (node (ref "CNC5") (pin "1") (pinfunction "1_1") (pintype "passive"))
      (node (ref "CNC7") (pin "1") (pinfunction "1_1") (pintype "passive"))
      (node (ref "DC3") (pin "2") (pinfunction "2_2") (pintype "passive"))
      (node (ref "DC4") (pin "2") (pinfunction "2_2") (pintype "passive"))
      (node (ref "DC5") (pin "2") (pinfunction "2_2") (pintype "passive"))
      (node (ref "FA2") (pin "1") (pinfunction "1_1") (pintype "passive"))
      (node (ref "QC1") (pin "3") (pinfunction "3_3") (pintype "passive"))
      (node (ref "RC47") (pin "2") (pinfunction "2_2") (pintype "passive"))
    )
    (net (code "8") (name "AUX.SHUT") (class "Default")
      (node (ref "CA121") (pin "2") (pinfunction "2_2") (pintype "passive"))
      (node (ref "CA122") (pin "2") (pinfunction "2_2") (pintype "passive"))
      (node (ref "RA187") (pin "1") (pinfunction "1_1") (pintype "passive"))
    )
    (net (code "9") (name "BUS+") (class "Default")
      (node (ref "CA70") (pin "2") (pinfunction "2_2") (pintype "passive"))
      (node (ref "CA75") (pin "2") (pinfunction "2_2") (pintype "passive"))
      (node (ref "CNBA3") (pin "1") (pinfunction "1_1") (pintype "passive"))
      (node (ref "DA6") (pin "1") (pinfunction "A_1") (pintype "passive"))
      (node (ref "RA110") (pin "2") (pinfunction "2_2") (pintype "passive"))
      (node (ref "RA125") (pin "1") (pinfunction "1_1") (pintype "passive"))
      (node (ref "RA173") (pin "2") (pinfunction "2_2") (pintype "passive"))
      (node (ref "TA1") (pin "8") (pinfunction "8_8") (pintype "passive"))
    )
    (net (code "10") (name "BUS-") (class "Default")
      (node (ref "BUS-") (pin "1") (pinfunction "1_1") (pintype "passive"))
      (node (ref "CA105") (pin "1") (pinfunction "1_1") (pintype "passive"))
      (node (ref "CA106") (pin "1") (pinfunction "1_1") (pintype "passive"))
      (node (ref "CA107") (pin "2") (pinfunction "2_2") (pintype "passive"))
      (node (ref "CA108") (pin "1") (pinfunction "1_1") (pintype "passive"))
      (node (ref "CA109") (pin "1") (pinfunction "1_1") (pintype "passive"))
      (node (ref "CA110") (pin "1") (pinfunction "1_1") (pintype "passive"))
      (node (ref "CA114") (pin "1") (pinfunction "1_1") (pintype "passive"))
      (node (ref "CA117") (pin "1") (pinfunction "1_1") (pintype "passive"))
      (node (ref "CA119") (pin "1") (pinfunction "1_1") (pintype "passive"))
      (node (ref "CA120") (pin "1") (pinfunction "1_1") (pintype "passive"))
      (node (ref "CA5") (pin "1") (pinfunction "1_1") (pintype "passive"))
      (node (ref "CA75") (pin "1") (pinfunction "1_1") (pintype "passive"))
      (node (ref "CA79") (pin "2") (pinfunction "2_2") (pintype "passive"))
      (node (ref "CA80") (pin "2") (pinfunction "2_2") (pintype "passive"))
      (node (ref "CA85") (pin "2") (pinfunction "2_2") (pintype "passive"))
      (node (ref "CA86") (pin "2") (pinfunction "2_2") (pintype "passive"))
      (node (ref "CA87") (pin "2") (pinfunction "2_2") (pintype "passive"))
      (node (ref "CA87a") (pin "2") (pinfunction "2_2") (pintype "passive"))
      (node (ref "CNBA3") (pin "2") (pinfunction "2_2") (pintype "passive"))
      (node (ref "LA8") (pin "1") (pinfunction "1_1") (pintype "passive"))
      (node (ref "LA9") (pin "1") (pinfunction "1_1") (pintype "passive"))
      (node (ref "QA11") (pin "2") (pinfunction "2_2") (pintype "passive"))
      (node (ref "QA8") (pin "2") (pinfunction "A_2") (pintype "passive"))
      (node (ref "RA122") (pin "2") (pinfunction "2_2") (pintype "passive"))
      (node (ref "RA152") (pin "1") (pinfunction "1_1") (pintype "passive"))
      (node (ref "RA153") (pin "1") (pinfunction "1_1") (pintype "passive"))
      (node (ref "RA154") (pin "1") (pinfunction "1_1") (pintype "passive"))
      (node (ref "RA164") (pin "1") (pinfunction "1_1") (pintype "passive"))
      (node (ref "RA167") (pin "1") (pinfunction "1_1") (pintype "passive"))
      (node (ref "RA169") (pin "1") (pinfunction "1_1") (pintype "passive"))
      (node (ref "RA179") (pin "1") (pinfunction "1_1") (pintype "passive"))
      (node (ref "RA185") (pin "1") (pinfunction "1_1") (pintype "passive"))
      (node (ref "TA1") (pin "2") (pinfunction "2_2") (pintype "passive"))
      (node (ref "UA12") (pin "5") (pinfunction "GND_5") (pintype "power_in"))
      (node (ref "UA13") (pin "4") (pinfunction "-_4") (pintype "power_in"))
      (node (ref "UA20") (pin "3") (pinfunction "3_3") (pintype "passive"))
    )
    (net (code "11") (name "FAN.CONTROL") (class "Default")
      (node (ref "RC78") (pin "2") (pinfunction "2_2") (pintype "passive"))
    )
    (net (code "12") (name "FAN5V.STATE1") (class "Default")
      (node (ref "DC7") (pin "1") (pinfunction "1_1") (pintype "passive"))
      (node (ref "RC81") (pin "2") (pinfunction "2_2") (pintype "passive"))
    )
    (net (code "13") (name "FAN5V.STATE2") (class "Default")
      (node (ref "DC8") (pin "1") (pinfunction "1_1") (pintype "passive"))
      (node (ref "RC82") (pin "2") (pinfunction "2_2") (pintype "passive"))
    )
    (net (code "14") (name "FAN5V.STATE3") (class "Default")
      (node (ref "DC30") (pin "1") (pinfunction "1_1") (pintype "passive"))
      (node (ref "RC85") (pin "2") (pinfunction "2_2") (pintype "passive"))
    )
    (net (code "15") (name "GND") (class "Default")
      (node (ref "CA112") (pin "1") (pinfunction "1_1") (pintype "passive"))
      (node (ref "CA115") (pin "1") (pinfunction "1_1") (pintype "passive"))
      (node (ref "CA121") (pin "1") (pinfunction "1_1") (pintype "passive"))
      (node (ref "CA122") (pin "1") (pinfunction "1_1") (pintype "passive"))
      (node (ref "CA5") (pin "2") (pinfunction "2_2") (pintype "passive"))
      (node (ref "CA74") (pin "1") (pinfunction "1_1") (pintype "passive"))
      (node (ref "CA77") (pin "1") (pinfunction "1_1") (pintype "passive"))
      (node (ref "CA78") (pin "2") (pinfunction "2_2") (pintype "passive"))
      (node (ref "CNA1") (pin "1") (pinfunction "1_1") (pintype "passive"))
      (node (ref "CNA1") (pin "4") (pinfunction "4_4") (pintype "passive"))
      (node (ref "DA7") (pin "1") (pinfunction "1_1") (pintype "passive"))
      (node (ref "LA17") (pin "2") (pinfunction "2_2") (pintype "passive"))
      (node (ref "LA5") (pin "2") (pinfunction "2_2") (pintype "passive"))
      (node (ref "LA8") (pin "2") (pinfunction "2_2") (pintype "passive"))
      (node (ref "LA9") (pin "2") (pinfunction "2_2") (pintype "passive"))
      (node (ref "LEDA1") (pin "2") (pinfunction "2_2") (pintype "passive"))
      (node (ref "QA12") (pin "2") (pinfunction "2_2") (pintype "passive"))
      (node (ref "QA13") (pin "1") (pinfunction "1_1") (pintype "passive"))
      (node (ref "QA7") (pin "1") (pinfunction "K_1") (pintype "passive"))
      (node (ref "RA116") (pin "2") (pinfunction "2_2") (pintype "passive"))
      (node (ref "RA117") (pin "1") (pinfunction "1_1") (pintype "passive"))
      (node (ref "RA163") (pin "1") (pinfunction "1_1") (pintype "passive"))
      (node (ref "RA184") (pin "1") (pinfunction "1_1") (pintype "passive"))
      (node (ref "RA188") (pin "1") (pinfunction "1_1") (pintype "passive"))
      (node (ref "UA10") (pin "6") (pinfunction "GND_6") (pintype "passive"))
      (node (ref "UA10") (pin "9") (pinfunction "GND_9") (pintype "power_in"))
    )
    (net (code "16") (name "GND-DRV") (class "Default")
      (node (ref "CA3") (pin "1") (pinfunction "1_1") (pintype "passive"))
      (node (ref "CA4") (pin "2") (pinfunction "2_2") (pintype "passive"))
      (node (ref "CA7") (pin "1") (pinfunction "1_1") (pintype "passive"))
      (node (ref "CA71") (pin "2") (pinfunction "2_2") (pintype "passive"))
      (node (ref "CA72") (pin "2") (pinfunction "2_2") (pintype "passive"))
      (node (ref "CA73") (pin "1") (pinfunction "1_1") (pintype "passive"))
      (node (ref "CA76") (pin "2") (pinfunction "2_2") (pintype "passive"))
      (node (ref "CA81") (pin "1") (pinfunction "1_1") (pintype "passive"))
      (node (ref "CA82") (pin "1") (pinfunction "1_1") (pintype "passive"))
      (node (ref "CA84") (pin "2") (pinfunction "2_2") (pintype "passive"))
      (node (ref "CNA23") (pin "1") (pinfunction "1_1") (pintype "passive"))
      (node (ref "CNA23") (pin "4") (pinfunction "4_4") (pintype "passive"))
      (node (ref "GND-DRV") (pin "1") (pinfunction "1_1") (pintype "passive"))
      (node (ref "LA17") (pin "1") (pinfunction "1_1") (pintype "passive"))
      (node (ref "LA5") (pin "1") (pinfunction "1_1") (pintype "passive"))
      (node (ref "RA112") (pin "2") (pinfunction "2_2") (pintype "passive"))
      (node (ref "RA119") (pin "1") (pinfunction "1_1") (pintype "passive"))
      (node (ref "RA120") (pin "1") (pinfunction "1_1") (pintype "passive"))
      (node (ref "TA1") (pin "15") (pinfunction "15_15") (pintype "passive"))
    )
    (net (code "17") (name "GND_FAN") (class "Default")
      (node (ref "CC194") (pin "1") (pinfunction "1_1") (pintype "passive"))
      (node (ref "CC197") (pin "2") (pinfunction "2_2") (pintype "passive"))
      (node (ref "CC29") (pin "1") (pinfunction "1_1") (pintype "passive"))
      (node (ref "CC50") (pin "2") (pinfunction "2_2") (pintype "passive"))
      (node (ref "CC51") (pin "1") (pinfunction "1_1") (pintype "passive"))
      (node (ref "CC74") (pin "1") (pinfunction "1_1") (pintype "passive"))
      (node (ref "CC81") (pin "2") (pinfunction "2_2") (pintype "passive"))
      (node (ref "LA13") (pin "2") (pinfunction "2_2") (pintype "passive"))
      (node (ref "LA19") (pin "2") (pinfunction "2_2") (pintype "passive"))
      (node (ref "QC44") (pin "3") (pinfunction "3_3") (pintype "passive"))
      (node (ref "QC46") (pin "3") (pinfunction "3_3") (pintype "passive"))
      (node (ref "RC80") (pin "1") (pinfunction "1_1") (pintype "passive"))
      (node (ref "RC86") (pin "1") (pinfunction "1_1") (pintype "passive"))
      (node (ref "RC89") (pin "1") (pinfunction "1_1") (pintype "passive"))
    )
    (net (code "18") (name "GND_S") (class "Default")
      (node (ref "CA1") (pin "1") (pinfunction "1_1") (pintype "passive"))
      (node (ref "CA100") (pin "2") (pinfunction "2_2") (pintype "passive"))
      (node (ref "CA101") (pin "2") (pinfunction "2_2") (pintype "passive"))
      (node (ref "CA102") (pin "1") (pinfunction "1_1") (pintype "passive"))
      (node (ref "CA103") (pin "2") (pinfunction "2_2") (pintype "passive"))
      (node (ref "CA2") (pin "2") (pinfunction "2_2") (pintype "passive"))
      (node (ref "CA92") (pin "2") (pinfunction "2_2") (pintype "passive"))
      (node (ref "CA93") (pin "1") (pinfunction "1_1") (pintype "passive"))
      (node (ref "CA94") (pin "1") (pinfunction "1_1") (pintype "passive"))
      (node (ref "CA96") (pin "2") (pinfunction "2_2") (pintype "passive"))
      (node (ref "CA98") (pin "2") (pinfunction "2_2") (pintype "passive"))
      (node (ref "DA12") (pin "1") (pinfunction "1_1") (pintype "passive"))
      (node (ref "GND_COM") (pin "1") (pinfunction "1_1") (pintype "passive"))
      (node (ref "LA13") (pin "1") (pinfunction "1_1") (pintype "passive"))
      (node (ref "LA19") (pin "1") (pinfunction "1_1") (pintype "passive"))
      (node (ref "RA129") (pin "2") (pinfunction "2_2") (pintype "passive"))
      (node (ref "RA132") (pin "2") (pinfunction "2_2") (pintype "passive"))
      (node (ref "RA137") (pin "1") (pinfunction "1_1") (pintype "passive"))
      (node (ref "RA138") (pin "1") (pinfunction "1_1") (pintype "passive"))
      (node (ref "RA140") (pin "1") (pinfunction "1_1") (pintype "passive"))
      (node (ref "TA1") (pin "11") (pinfunction "11_11") (pintype "passive"))
      (node (ref "UA11") (pin "6") (pinfunction "GND_6") (pintype "passive"))
      (node (ref "UA11") (pin "9") (pinfunction "GND_9") (pintype "power_in"))
    )
    (net (code "19") (name "Net-(CA1-Pad2)") (class "Default")
      (node (ref "CA1") (pin "2") (pinfunction "2_2") (pintype "passive"))
      (node (ref "CA91") (pin "2") (pinfunction "2_2") (pintype "passive"))
      (node (ref "CA96") (pin "1") (pinfunction "1_1") (pintype "passive"))
      (node (ref "DA11") (pin "2") (pinfunction "2_2") (pintype "passive"))
      (node (ref "DA11") (pin "4") (pinfunction "4_4") (pintype "passive"))
      (node (ref "LA10") (pin "1") (pinfunction "1_1") (pintype "passive"))
    )
    (net (code "20") (name "Net-(CA4-Pad1)") (class "Default")
      (node (ref "CA4") (pin "1") (pinfunction "1_1") (pintype "passive"))
      (node (ref "CA6") (pin "2") (pinfunction "2_2") (pintype "passive"))
      (node (ref "CA81") (pin "2") (pinfunction "2_2") (pintype "passive"))
      (node (ref "CA83") (pin "2") (pinfunction "2_2") (pintype "passive"))
      (node (ref "DA10") (pin "1") (pinfunction "1_1") (pintype "passive"))
      (node (ref "LA6") (pin "1") (pinfunction "1_1") (pintype "passive"))
    )
    (net (code "21") (name "Net-(CA6-Pad1)") (class "Default")
      (node (ref "CA6") (pin "1") (pinfunction "1_1") (pintype "passive"))
      (node (ref "CA83") (pin "1") (pinfunction "1_1") (pintype "passive"))
      (node (ref "RA118") (pin "2") (pinfunction "2_2") (pintype "passive"))
      (node (ref "RA121") (pin "2") (pinfunction "2_2") (pintype "passive"))
    )
    (net (code "22") (name "Net-(CA68-Pad1)") (class "Default")
      (node (ref "CA68") (pin "1") (pinfunction "1_1") (pintype "passive"))
      (node (ref "RA108") (pin "2") (pinfunction "2_2") (pintype "passive"))
      (node (ref "RA109") (pin "2") (pinfunction "2_2") (pintype "passive"))
    )
    (net (code "23") (name "Net-(CA73-Pad2)") (class "Default")
      (node (ref "CA73") (pin "2") (pinfunction "2_2") (pintype "passive"))
      (node (ref "CA76") (pin "1") (pinfunction "1_1") (pintype "passive"))
      (node (ref "LA16") (pin "1") (pinfunction "1_1") (pintype "passive"))
      (node (ref "LA2") (pin "2") (pinfunction "2_2") (pintype "passive"))
      (node (ref "LA3") (pin "1") (pinfunction "1_1") (pintype "passive"))
      (node (ref "RA112") (pin "1") (pinfunction "1_1") (pintype "passive"))
    )
    (net (code "24") (name "Net-(CA77-Pad2)") (class "Default")
      (node (ref "CA77") (pin "2") (pinfunction "2_2") (pintype "passive"))
      (node (ref "CA78") (pin "1") (pinfunction "1_1") (pintype "passive"))
      (node (ref "LA4") (pin "2") (pinfunction "2_2") (pintype "passive"))
      (node (ref "RA111") (pin "2") (pinfunction "2_2") (pintype "passive"))
      (node (ref "RA115") (pin "2") (pinfunction "2_2") (pintype "passive"))
    )
    (net (code "25") (name "Net-(CA79-Pad1)") (class "Default")
      (node (ref "CA79") (pin "1") (pinfunction "1_1") (pintype "passive"))
      (node (ref "CA80") (pin "1") (pinfunction "1_1") (pintype "passive"))
      (node (ref "QA6") (pin "2") (pinfunction "2_2") (pintype "passive"))
      (node (ref "RA123") (pin "2") (pinfunction "2_2") (pintype "passive"))
      (node (ref "RA147") (pin "2") (pinfunction "2_2") (pintype "passive"))
    )
    (net (code "26") (name "Net-(CA82-Pad2)") (class "Default")
      (node (ref "CA82") (pin "2") (pinfunction "2_2") (pintype "passive"))
      (node (ref "CA84") (pin "1") (pinfunction "1_1") (pintype "passive"))
      (node (ref "LA6") (pin "2") (pinfunction "2_2") (pintype "passive"))
      (node (ref "LA7") (pin "1") (pinfunction "1_1") (pintype "passive"))
      (node (ref "RA119") (pin "2") (pinfunction "2_2") (pintype "passive"))
      (node (ref "RA120") (pin "2") (pinfunction "2_2") (pintype "passive"))
    )
    (net (code "27") (name "Net-(CA91-Pad1)") (class "Default")
      (node (ref "CA91") (pin "1") (pinfunction "1_1") (pintype "passive"))
      (node (ref "RA127") (pin "2") (pinfunction "2_2") (pintype "passive"))
      (node (ref "RA131") (pin "2") (pinfunction "2_2") (pintype "passive"))
    )
    (net (code "28") (name "Net-(CA92-Pad1)") (class "Default")
      (node (ref "CA92") (pin "1") (pinfunction "1_1") (pintype "passive"))
      (node (ref "CA93") (pin "2") (pinfunction "2_2") (pintype "passive"))
      (node (ref "LA10") (pin "2") (pinfunction "2_2") (pintype "passive"))
      (node (ref "LA11") (pin "1") (pinfunction "1_1") (pintype "passive"))
      (node (ref "LA18") (pin "1") (pinfunction "1_1") (pintype "passive"))
      (node (ref "RA129") (pin "1") (pinfunction "1_1") (pintype "passive"))
      (node (ref "RA132") (pin "1") (pinfunction "1_1") (pintype "passive"))
    )
    (net (code "29") (name "Net-(CA100-Pad1)") (class "Default")
      (node (ref "CA100") (pin "1") (pinfunction "1_1") (pintype "passive"))
      (node (ref "CA98") (pin "1") (pinfunction "1_1") (pintype "passive"))
      (node (ref "LA14") (pin "2") (pinfunction "2_2") (pintype "passive"))
      (node (ref "LA15") (pin "1") (pinfunction "1_1") (pintype "passive"))
      (node (ref "LA20") (pin "1") (pinfunction "1_1") (pintype "passive"))
      (node (ref "RA137") (pin "2") (pinfunction "2_2") (pintype "passive"))
    )
    (net (code "30") (name "Net-(CA101-Pad1)") (class "Default")
      (node (ref "CA101") (pin "1") (pinfunction "1_1") (pintype "passive"))
      (node (ref "CA104") (pin "2") (pinfunction "2_2") (pintype "passive"))
      (node (ref "CA2") (pin "1") (pinfunction "1_1") (pintype "passive"))
      (node (ref "DA13") (pin "2") (pinfunction "2_2") (pintype "passive"))
      (node (ref "DA13") (pin "4") (pinfunction "4_4") (pintype "passive"))
      (node (ref "LA14") (pin "1") (pinfunction "1_1") (pintype "passive"))
    )
    (net (code "31") (name "Net-(CA102-Pad2)") (class "Default")
      (node (ref "CA102") (pin "2") (pinfunction "2_2") (pintype "passive"))
      (node (ref "CA103") (pin "1") (pinfunction "1_1") (pintype "passive"))
      (node (ref "LA12") (pin "2") (pinfunction "2_2") (pintype "passive"))
      (node (ref "RA126") (pin "2") (pinfunction "2_2") (pintype "passive"))
      (node (ref "RA134") (pin "2") (pinfunction "2_2") (pintype "passive"))
    )
    (net (code "32") (name "Net-(CA104-Pad1)") (class "Default")
      (node (ref "CA104") (pin "1") (pinfunction "1_1") (pintype "passive"))
      (node (ref "RA143") (pin "2") (pinfunction "2_2") (pintype "passive"))
      (node (ref "RA144") (pin "2") (pinfunction "2_2") (pintype "passive"))
    )
    (net (code "33") (name "Net-(CA110-Pad2)") (class "Default")
      (node (ref "CA110") (pin "2") (pinfunction "2_2") (pintype "passive"))
      (node (ref "CA114") (pin "2") (pinfunction "2_2") (pintype "passive"))
      (node (ref "DA15") (pin "1") (pinfunction "1_1") (pintype "passive"))
      (node (ref "QA6") (pin "3") (pinfunction "3_3") (pintype "passive"))
      (node (ref "RA156") (pin "2") (pinfunction "2_2") (pintype "passive"))
    )
    (net (code "34") (name "Net-(CA113-Pad2)") (class "Default")
      (node (ref "CA113") (pin "2") (pinfunction "2_2") (pintype "passive"))
      (node (ref "RA157") (pin "1") (pinfunction "1_1") (pintype "passive"))
      (node (ref "RA162") (pin "1") (pinfunction "1_1") (pintype "passive"))
      (node (ref "RA164") (pin "2") (pinfunction "2_2") (pintype "passive"))
      (node (ref "UA13") (pin "3") (pintype "passive"))
      (node (ref "UA13") (pin "5") (pintype "passive"))
    )
    (net (code "35") (name "Net-(CA116-Pad1)") (class "Default")
      (node (ref "CA116") (pin "1") (pinfunction "1_1") (pintype "passive"))
      (node (ref "CA118") (pin "1") (pinfunction "1_1") (pintype "passive"))
      (node (ref "QA12") (pin "1") (pinfunction "1_1") (pintype "passive"))
      (node (ref "RA180") (pin "1") (pinfunction "1_1") (pintype "passive"))
      (node (ref "RA184") (pin "2") (pinfunction "2_2") (pintype "passive"))
    )
    (net (code "36") (name "Net-(CA117-Pad2)") (class "Default")
      (node (ref "CA117") (pin "2") (pinfunction "2_2") (pintype "passive"))
      (node (ref "RA172") (pin "2") (pinfunction "2_2") (pintype "passive"))
      (node (ref "RA179") (pin "2") (pinfunction "2_2") (pintype "passive"))
      (node (ref "UA13") (pin "2") (pintype "passive"))
    )
    (net (code "37") (name "Net-(CA118-Pad2)") (class "Default")
      (node (ref "CA118") (pin "2") (pinfunction "2_2") (pintype "passive"))
      (node (ref "RA181") (pin "1") (pinfunction "1_1") (pintype "passive"))
    )
    (net (code "38") (name "Net-(CA119-Pad2)") (class "Default")
      (node (ref "CA119") (pin "2") (pinfunction "2_2") (pintype "passive"))
      (node (ref "RA178") (pin "1") (pinfunction "1_1") (pintype "passive"))
      (node (ref "RA185") (pin "2") (pinfunction "2_2") (pintype "passive"))
      (node (ref "UA14") (pin "3") (pinfunction "3_3") (pintype "passive"))
    )
    (net (code "39") (name "Net-(CA120-Pad2)") (class "Default")
      (node (ref "CA120") (pin "2") (pinfunction "2_2") (pintype "passive"))
      (node (ref "DA16") (pin "1") (pinfunction "1_1") (pintype "passive"))
      (node (ref "RA182") (pin "1") (pinfunction "1_1") (pintype "passive"))
      (node (ref "RA183") (pin "1") (pinfunction "1_1") (pintype "passive"))
    )
    (net (code "40") (name "Net-(CC22-Pad2)") (class "Default")
      (node (ref "CC22") (pin "2") (pinfunction "2_2") (pintype "passive"))
      (node (ref "CC25") (pin "2") (pinfunction "2_2") (pintype "passive"))
      (node (ref "CC28") (pin "2") (pinfunction "2_2") (pintype "passive"))
      (node (ref "CNC4") (pin "3") (pinfunction "3_3") (pintype "passive"))
      (node (ref "CNC5") (pin "3") (pinfunction "3_3") (pintype "passive"))
      (node (ref "CNC7") (pin "3") (pinfunction "3_3") (pintype "passive"))
      (node (ref "DC3") (pin "1") (pinfunction "1_1") (pintype "passive"))
      (node (ref "DC4") (pin "1") (pinfunction "1_1") (pintype "passive"))
      (node (ref "DC5") (pin "1") (pinfunction "1_1") (pintype "passive"))
      (node (ref "QC44") (pin "2") (pinfunction "2_2") (pintype "passive"))
      (node (ref "QC44") (pin "4") (pinfunction "4_4") (pintype "passive"))
    )
    (net (code "41") (name "Net-(CC29-Pad2)") (class "Default")
      (node (ref "CC29") (pin "2") (pinfunction "2_2") (pintype "passive"))
      (node (ref "QC45") (pin "1") (pinfunction "1_1") (pintype "passive"))
      (node (ref "RC78") (pin "1") (pinfunction "1_1") (pintype "passive"))
      (node (ref "RC89") (pin "2") (pinfunction "2_2") (pintype "passive"))
    )
    (net (code "42") (name "Net-(CNC4-Pad2)") (class "Default")
      (node (ref "CNC4") (pin "2") (pinfunction "2_2") (pintype "passive"))
      (node (ref "DC8") (pin "2") (pinfunction "2_2") (pintype "passive"))
    )
    (net (code "43") (name "Net-(CNC5-Pad2)") (class "Default")
      (node (ref "CNC5") (pin "2") (pinfunction "2_2") (pintype "passive"))
      (node (ref "DC7") (pin "2") (pinfunction "2_2") (pintype "passive"))
    )
    (net (code "44") (name "Net-(CNC7-Pad2)") (class "Default")
      (node (ref "CNC7") (pin "2") (pinfunction "2_2") (pintype "passive"))
      (node (ref "DC30") (pin "2") (pinfunction "2_2") (pintype "passive"))
    )
    (net (code "45") (name "Net-(DA5-Pad1)") (class "Default")
      (node (ref "DA5") (pin "1") (pinfunction "1_1") (pintype "passive"))
      (node (ref "DA5") (pin "3") (pinfunction "3_3") (pintype "passive"))
      (node (ref "RA108") (pin "1") (pinfunction "1_1") (pintype "passive"))
      (node (ref "RA109") (pin "1") (pinfunction "1_1") (pintype "passive"))
      (node (ref "TA1") (pin "14") (pinfunction "14_14") (pintype "passive"))
    )
    (net (code "46") (name "Net-(DA6-K)") (class "Default")
      (node (ref "CA70") (pin "1") (pinfunction "1_1") (pintype "passive"))
      (node (ref "DA6") (pin "2") (pinfunction "K_2") (pintype "passive"))
      (node (ref "RA110") (pin "1") (pinfunction "1_1") (pintype "passive"))
      (node (ref "RA114") (pin "1") (pinfunction "1_1") (pintype "passive"))
    )
    (net (code "47") (name "Net-(DA8-Pad1)") (class "Default")
      (node (ref "DA8") (pin "1") (pinfunction "1_1") (pintype "passive"))
      (node (ref "QA5") (pin "2") (pintype "passive"))
      (node (ref "TA1") (pin "4") (pinfunction "4_4") (pintype "passive"))
      (node (ref "Vd1") (pin "1") (pinfunction "1_1") (pintype "passive"))
    )
    (net (code "48") (name "Net-(DA8-Pad2)") (class "Default")
      (node (ref "DA8") (pin "2") (pinfunction "2_2") (pintype "passive"))
      (node (ref "RA114") (pin "2") (pinfunction "2_2") (pintype "passive"))
    )
    (net (code "49") (name "Net-(DA9-A)") (class "Default")
      (node (ref "DA9") (pin "1") (pinfunction "A_1") (pintype "passive"))
      (node (ref "TA1") (pin "1") (pinfunction "1_1") (pintype "passive"))
    )
    (net (code "50") (name "Net-(DA9-K)") (class "Default")
      (node (ref "DA9") (pin "2") (pinfunction "K_2") (pintype "passive"))
      (node (ref "RA123") (pin "1") (pinfunction "1_1") (pintype "passive"))
    )
    (net (code "51") (name "Net-(DA10-Pad2)") (class "Default")
      (node (ref "DA10") (pin "2") (pinfunction "2_2") (pintype "passive"))
      (node (ref "RA118") (pin "1") (pinfunction "1_1") (pintype "passive"))
      (node (ref "RA121") (pin "1") (pinfunction "1_1") (pintype "passive"))
      (node (ref "TA1") (pin "16") (pinfunction "16_16") (pintype "passive"))
    )
    (net (code "52") (name "Net-(DA11-Pad1)") (class "Default")
      (node (ref "DA11") (pin "1") (pinfunction "1_1") (pintype "passive"))
      (node (ref "DA11") (pin "3") (pinfunction "3_3") (pintype "passive"))
      (node (ref "RA127") (pin "1") (pinfunction "1_1") (pintype "passive"))
      (node (ref "RA131") (pin "1") (pinfunction "1_1") (pintype "passive"))
      (node (ref "TA1") (pin "9") (pinfunction "9_9") (pintype "passive"))
    )
    (net (code "53") (name "Net-(DA13-Pad1)") (class "Default")
      (node (ref "DA13") (pin "1") (pinfunction "1_1") (pintype "passive"))
      (node (ref "DA13") (pin "3") (pinfunction "3_3") (pintype "passive"))
      (node (ref "RA143") (pin "1") (pinfunction "1_1") (pintype "passive"))
      (node (ref "RA144") (pin "1") (pinfunction "1_1") (pintype "passive"))
      (node (ref "TA1") (pin "10") (pinfunction "10_10") (pintype "passive"))
    )
    (net (code "54") (name "Net-(DA14-Pad1)") (class "Default")
      (node (ref "DA14") (pin "1") (pinfunction "1_1") (pintype "passive"))
      (node (ref "RA145") (pin "1") (pinfunction "1_1") (pintype "passive"))
    )
    (net (code "55") (name "Net-(DA17-K)") (class "Default")
      (node (ref "DA17") (pin "2") (pinfunction "K_2") (pintype "passive"))
      (node (ref "RA186") (pin "1") (pinfunction "1_1") (pintype "passive"))
      (node (ref "RA215") (pin "1") (pinfunction "1_1") (pintype "passive"))
      (node (ref "UA20") (pin "4") (pinfunction "4_4") (pintype "passive"))
    )
    (net (code "56") (name "Net-(FA2-Pad2)") (class "Default")
      (node (ref "FA2") (pin "2") (pinfunction "2_2") (pintype "passive"))
      (node (ref "LA11") (pin "2") (pinfunction "2_2") (pintype "passive"))
      (node (ref "LA18") (pin "2") (pinfunction "2_2") (pintype "passive"))
    )
    (net (code "57") (name "Net-(FA3-Pad2)") (class "Default")
      (node (ref "FA3") (pin "2") (pinfunction "2_2") (pintype "passive"))
      (node (ref "LA15") (pin "2") (pinfunction "2_2") (pintype "passive"))
      (node (ref "LA20") (pin "2") (pinfunction "2_2") (pintype "passive"))
    )
    (net (code "58") (name "Net-(LEDA1-Pad1)") (class "Default")
      (node (ref "LEDA1") (pin "1") (pinfunction "1_1") (pintype "passive"))
      (node (ref "RA192") (pin "1") (pinfunction "1_1") (pintype "passive"))
    )
    (net (code "59") (name "Net-(QA5-Pad1)") (class "Default")
      (node (ref "QA5") (pin "1") (pintype "passive"))
      (node (ref "RA145") (pin "2") (pinfunction "2_2") (pintype "passive"))
      (node (ref "RA146") (pin "2") (pinfunction "2_2") (pintype "passive"))
      (node (ref "RA148") (pin "2") (pinfunction "2_2") (pintype "passive"))
      (node (ref "RA150") (pin "1") (pinfunction "1_1") (pintype "passive"))
    )
    (net (code "60") (name "Net-(QA5-Pad3)") (class "Default")
      (node (ref "QA5") (pin "3") (pintype "passive"))
      (node (ref "RA149") (pin "1") (pinfunction "1_1") (pintype "passive"))
      (node (ref "RA150") (pin "2") (pinfunction "2_2") (pintype "passive"))
      (node (ref "RA152") (pin "2") (pinfunction "2_2") (pintype "passive"))
      (node (ref "RA153") (pin "2") (pinfunction "2_2") (pintype "passive"))
      (node (ref "RA154") (pin "2") (pinfunction "2_2") (pintype "passive"))
    )
    (net (code "61") (name "Net-(QA7-A)") (class "Default")
      (node (ref "CA116") (pin "2") (pinfunction "2_2") (pintype "passive"))
      (node (ref "QA12") (pin "3") (pinfunction "3_3") (pintype "passive"))
      (node (ref "QA7") (pin "3") (pinfunction "A_3") (pintype "passive"))
      (node (ref "RA168") (pin "1") (pinfunction "1_1") (pintype "passive"))
      (node (ref "RA181") (pin "2") (pinfunction "2_2") (pintype "passive"))
      (node (ref "UA14") (pin "2") (pinfunction "2_2") (pintype "passive"))
    )
    (net (code "62") (name "Net-(QA7-G)") (class "Default")
      (node (ref "CA112") (pin "2") (pinfunction "2_2") (pintype "passive"))
      (node (ref "QA7") (pin "2") (pinfunction "G_2") (pintype "passive"))
      (node (ref "RA155") (pin "1") (pinfunction "1_1") (pintype "passive"))
      (node (ref "RA163") (pin "2") (pinfunction "2_2") (pintype "passive"))
    )
    (net (code "63") (name "Net-(QA8-K)") (class "Default")
      (node (ref "QA6") (pin "1") (pinfunction "1_1") (pintype "passive"))
      (node (ref "QA8") (pin "3") (pinfunction "K_3") (pintype "passive"))
      (node (ref "RA147") (pin "1") (pinfunction "1_1") (pintype "passive"))
    )
    (net (code "64") (name "Net-(QA8-R)") (class "Default")
      (node (ref "QA8") (pin "1") (pinfunction "R_1") (pintype "passive"))
      (node (ref "RA156") (pin "1") (pinfunction "1_1") (pintype "passive"))
      (node (ref "RA167") (pin "2") (pinfunction "2_2") (pintype "passive"))
    )
    (net (code "65") (name "Net-(QA10-Pad2)") (class "Default")
      (node (ref "QA10") (pin "2") (pinfunction "2_2") (pintype "passive"))
      (node (ref "RA169") (pin "2") (pinfunction "2_2") (pintype "passive"))
    )
    (net (code "66") (name "Net-(QA10-Pad3)") (class "Default")
      (node (ref "QA10") (pin "3") (pinfunction "3_3") (pintype "passive"))
      (node (ref "QA9") (pin "1") (pinfunction "1_1") (pintype "passive"))
      (node (ref "RA165") (pin "2") (pinfunction "2_2") (pintype "passive"))
    )
    (net (code "67") (name "Net-(QA11-Pad1)") (class "Default")
      (node (ref "QA11") (pin "1") (pinfunction "1_1") (pintype "passive"))
      (node (ref "RA183") (pin "2") (pinfunction "2_2") (pintype "passive"))
    )
    (net (code "68") (name "Net-(QA13-Pad2)") (class "Default")
      (node (ref "QA13") (pin "2") (pinfunction "2_2") (pintype "passive"))
      (node (ref "RA187") (pin "2") (pinfunction "2_2") (pintype "passive"))
      (node (ref "RA188") (pin "2") (pinfunction "2_2") (pintype "passive"))
    )
    (net (code "69") (name "Net-(QA13-Pad3)") (class "Default")
      (node (ref "QA13") (pin "3") (pinfunction "3_3") (pintype "passive"))
      (node (ref "RA204") (pin "1") (pinfunction "1_1") (pintype "passive"))
      (node (ref "UA20") (pin "2") (pinfunction "2_2") (pintype "passive"))
    )
    (net (code "70") (name "Net-(QC1-Pad1)") (class "Default")
      (node (ref "QC1") (pin "1") (pinfunction "1_1") (pintype "passive"))
      (node (ref "QC46") (pin "1") (pinfunction "1_1") (pintype "passive"))
      (node (ref "RC49") (pin "2") (pinfunction "2_2") (pintype "passive"))
    )
    (net (code "71") (name "Net-(QC1-Pad2)") (class "Default")
      (node (ref "QC1") (pin "2") (pinfunction "2_2") (pintype "passive"))
      (node (ref "QC46") (pin "2") (pinfunction "2_2") (pintype "passive"))
      (node (ref "RC77") (pin "1") (pinfunction "1_1") (pintype "passive"))
    )
    (net (code "72") (name "Net-(QC44-Pad1)") (class "Default")
      (node (ref "QC44") (pin "1") (pinfunction "1_1") (pintype "passive"))
      (node (ref "RC77") (pin "2") (pinfunction "2_2") (pintype "passive"))
      (node (ref "RC80") (pin "2") (pinfunction "2_2") (pintype "passive"))
    )
    (net (code "73") (name "Net-(QC45-Pad2)") (class "Default")
      (node (ref "QC45") (pin "2") (pinfunction "2_2") (pintype "passive"))
      (node (ref "RC86") (pin "2") (pinfunction "2_2") (pintype "passive"))
    )
    (net (code "74") (name "Net-(QC45-Pad3)") (class "Default")
      (node (ref "QC45") (pin "3") (pinfunction "3_3") (pintype "passive"))
      (node (ref "RC47") (pin "1") (pinfunction "1_1") (pintype "passive"))
      (node (ref "RC49") (pin "1") (pinfunction "1_1") (pintype "passive"))
    )
    (net (code "75") (name "Net-(RA124-Pad2)") (class "Default")
      (node (ref "RA124") (pin "2") (pinfunction "2_2") (pintype "passive"))
      (node (ref "RA128") (pin "1") (pinfunction "1_1") (pintype "passive"))
    )
    (net (code "76") (name "Net-(RA125-Pad2)") (class "Default")
      (node (ref "RA125") (pin "2") (pinfunction "2_2") (pintype "passive"))
      (node (ref "RA130") (pin "1") (pinfunction "1_1") (pintype "passive"))
    )
    (net (code "77") (name "Net-(RA128-Pad2)") (class "Default")
      (node (ref "RA128") (pin "2") (pinfunction "2_2") (pintype "passive"))
      (node (ref "RA135") (pin "1") (pinfunction "1_1") (pintype "passive"))
    )
    (net (code "78") (name "Net-(RA130-Pad2)") (class "Default")
      (node (ref "RA130") (pin "2") (pinfunction "2_2") (pintype "passive"))
      (node (ref "RA136") (pin "1") (pinfunction "1_1") (pintype "passive"))
    )
    (net (code "79") (name "Net-(RA135-Pad2)") (class "Default")
      (node (ref "RA135") (pin "2") (pinfunction "2_2") (pintype "passive"))
      (node (ref "RA139") (pin "1") (pinfunction "1_1") (pintype "passive"))
    )
    (net (code "80") (name "Net-(RA136-Pad2)") (class "Default")
      (node (ref "RA136") (pin "2") (pinfunction "2_2") (pintype "passive"))
      (node (ref "RA141") (pin "1") (pinfunction "1_1") (pintype "passive"))
    )
    (net (code "81") (name "Net-(RA139-Pad2)") (class "Default")
      (node (ref "RA139") (pin "2") (pinfunction "2_2") (pintype "passive"))
      (node (ref "RA142") (pin "2") (pinfunction "2_2") (pintype "passive"))
    )
    (net (code "82") (name "Net-(RA141-Pad2)") (class "Default")
      (node (ref "RA141") (pin "2") (pinfunction "2_2") (pintype "passive"))
      (node (ref "RA142") (pin "1") (pinfunction "1_1") (pintype "passive"))
    )
    (net (code "83") (name "Net-(RA155-Pad2)") (class "Default")
      (node (ref "RA155") (pin "2") (pinfunction "2_2") (pintype "passive"))
      (node (ref "ZDA1") (pin "1") (pinfunction "1_1") (pintype "passive"))
    )
    (net (code "84") (name "Net-(RA157-Pad2)") (class "Default")
      (node (ref "RA157") (pin "2") (pinfunction "2_2") (pintype "passive"))
      (node (ref "RA171") (pin "1") (pinfunction "1_1") (pintype "passive"))
      (node (ref "UA13") (pin "1") (pintype "passive"))
      (node (ref "UA13") (pin "6") (pintype "passive"))
    )
    (net (code "85") (name "Net-(RA158-Pad1)") (class "Default")
      (node (ref "RA158") (pin "1") (pinfunction "1_1") (pintype "passive"))
      (node (ref "RA159") (pin "1") (pinfunction "1_1") (pintype "passive"))
      (node (ref "RA160") (pin "1") (pinfunction "1_1") (pintype "passive"))
      (node (ref "RA168") (pin "2") (pinfunction "2_2") (pintype "passive"))
      (node (ref "UA14") (pin "1") (pinfunction "1_1") (pintype "passive"))
    )
    (net (code "86") (name "Net-(RA161-Pad1)") (class "Default")
      (node (ref "RA161") (pin "1") (pinfunction "1_1") (pintype "passive"))
      (node (ref "RA162") (pin "2") (pinfunction "2_2") (pintype "passive"))
    )
    (net (code "87") (name "Net-(RA170-Pad1)") (class "Default")
      (node (ref "RA170") (pin "1") (pinfunction "1_1") (pintype "passive"))
      (node (ref "RA180") (pin "2") (pinfunction "2_2") (pintype "passive"))
    )
    (net (code "88") (name "Net-(RA172-Pad1)") (class "Default")
      (node (ref "RA172") (pin "1") (pinfunction "1_1") (pintype "passive"))
      (node (ref "RA175") (pin "2") (pinfunction "2_2") (pintype "passive"))
    )
    (net (code "89") (name "Net-(RA173-Pad1)") (class "Default")
      (node (ref "RA173") (pin "1") (pinfunction "1_1") (pintype "passive"))
      (node (ref "RA174") (pin "1") (pinfunction "1_1") (pintype "passive"))
    )
    (net (code "90") (name "Net-(RA174-Pad2)") (class "Default")
      (node (ref "RA174") (pin "2") (pinfunction "2_2") (pintype "passive"))
      (node (ref "RA177") (pin "1") (pinfunction "1_1") (pintype "passive"))
    )
    (net (code "91") (name "Net-(RA175-Pad1)") (class "Default")
      (node (ref "RA175") (pin "1") (pinfunction "1_1") (pintype "passive"))
      (node (ref "RA176") (pin "1") (pinfunction "1_1") (pintype "passive"))
    )
    (net (code "92") (name "Net-(RA176-Pad2)") (class "Default")
      (node (ref "RA176") (pin "2") (pinfunction "2_2") (pintype "passive"))
      (node (ref "RA177") (pin "2") (pinfunction "2_2") (pintype "passive"))
    )
    (net (code "93") (name "Net-(RA198-Pad1)") (class "Default")
      (node (ref "RA198") (pin "1") (pinfunction "1_1") (pintype "passive"))
      (node (ref "RA200") (pin "1") (pinfunction "1_1") (pintype "passive"))
      (node (ref "RA204") (pin "2") (pinfunction "2_2") (pintype "passive"))
      (node (ref "UA20") (pin "1") (pinfunction "1_1") (pintype "passive"))
    )
    (net (code "94") (name "Net-(UA10-BOOT)") (class "Default")
      (node (ref "CA69") (pin "1") (pinfunction "1_1") (pintype "passive"))
      (node (ref "UA10") (pin "1") (pinfunction "BOOT_1") (pintype "passive"))
    )
    (net (code "95") (name "Net-(UA10-ENA)") (class "Default")
      (node (ref "RA113") (pin "2") (pinfunction "2_2") (pintype "passive"))
      (node (ref "RA116") (pin "1") (pinfunction "1_1") (pintype "passive"))
      (node (ref "UA10") (pin "5") (pinfunction "ENA_5") (pintype "passive"))
    )
    (net (code "96") (name "Net-(UA10-PH)") (class "Default")
      (node (ref "CA69") (pin "2") (pinfunction "2_2") (pintype "passive"))
      (node (ref "DA7") (pin "2") (pinfunction "2_2") (pintype "passive"))
      (node (ref "LA4") (pin "1") (pinfunction "1_1") (pintype "passive"))
      (node (ref "UA10") (pin "8") (pinfunction "PH_8") (pintype "power_in"))
    )
    (net (code "97") (name "Net-(UA10-VSENSE)") (class "Default")
      (node (ref "RA115") (pin "1") (pinfunction "1_1") (pintype "passive"))
      (node (ref "RA117") (pin "2") (pinfunction "2_2") (pintype "passive"))
      (node (ref "UA10") (pin "4") (pinfunction "VSENSE_4") (pintype "power_in"))
    )
    (net (code "98") (name "Net-(UA11-BOOT)") (class "Default")
      (node (ref "CA90") (pin "1") (pinfunction "1_1") (pintype "passive"))
      (node (ref "UA11") (pin "1") (pinfunction "BOOT_1") (pintype "passive"))
    )
    (net (code "99") (name "Net-(UA11-ENA)") (class "Default")
      (node (ref "RA133") (pin "2") (pinfunction "2_2") (pintype "passive"))
      (node (ref "RA138") (pin "2") (pinfunction "2_2") (pintype "passive"))
      (node (ref "UA11") (pin "5") (pinfunction "ENA_5") (pintype "passive"))
    )
    (net (code "100") (name "Net-(UA11-PH)") (class "Default")
      (node (ref "CA90") (pin "2") (pinfunction "2_2") (pintype "passive"))
      (node (ref "DA12") (pin "2") (pinfunction "2_2") (pintype "passive"))
      (node (ref "LA12") (pin "1") (pinfunction "1_1") (pintype "passive"))
      (node (ref "UA11") (pin "8") (pinfunction "PH_8") (pintype "power_in"))
    )
    (net (code "101") (name "Net-(UA11-VSENSE)") (class "Default")
      (node (ref "RA134") (pin "1") (pinfunction "1_1") (pintype "passive"))
      (node (ref "RA140") (pin "2") (pinfunction "2_2") (pintype "passive"))
      (node (ref "UA11") (pin "4") (pinfunction "VSENSE_4") (pintype "power_in"))
    )
    (net (code "102") (name "Net-(UA12-CS)") (class "Default")
      (node (ref "CA106") (pin "2") (pinfunction "2_2") (pintype "passive"))
      (node (ref "RA149") (pin "2") (pinfunction "2_2") (pintype "passive"))
      (node (ref "UA12") (pin "3") (pinfunction "CS_3") (pintype "passive"))
    )
    (net (code "103") (name "Net-(UA12-OUT)") (class "Default")
      (node (ref "DA14") (pin "2") (pinfunction "2_2") (pintype "passive"))
      (node (ref "RA146") (pin "1") (pinfunction "1_1") (pintype "passive"))
      (node (ref "RA148") (pin "1") (pinfunction "1_1") (pintype "passive"))
      (node (ref "UA12") (pin "6") (pinfunction "OUT_6") (pintype "passive"))
    )
    (net (code "104") (name "Net-(UA12-RT{slash}CT)") (class "Default")
      (node (ref "CA108") (pin "2") (pinfunction "2_2") (pintype "passive"))
      (node (ref "RA151") (pin "2") (pinfunction "2_2") (pintype "passive"))
      (node (ref "UA12") (pin "4") (pinfunction "RT/CT_4") (pintype "passive"))
    )
    (net (code "105") (name "Net-(UA12-VFB)") (class "Default")
      (node (ref "CA111") (pin "1") (pinfunction "1_1") (pintype "passive"))
      (node (ref "RA166") (pin "2") (pinfunction "2_2") (pintype "passive"))
      (node (ref "RA178") (pin "2") (pinfunction "2_2") (pintype "passive"))
      (node (ref "UA12") (pin "2") (pinfunction "VFB_2") (pintype "passive"))
    )
    (net (code "106") (name "VCC") (class "Default")
      (node (ref "CA109") (pin "2") (pinfunction "2_2") (pintype "passive"))
      (node (ref "QA9") (pin "3") (pinfunction "3_3") (pintype "passive"))
      (node (ref "UA13") (pin "8") (pinfunction "+_8") (pintype "power_in"))
      (node (ref "VCC") (pin "1") (pinfunction "1_1") (pintype "passive"))
    )
    (net (code "107") (name "VCC-AUX") (class "Default")
      (node (ref "CA85") (pin "1") (pinfunction "1_1") (pintype "passive"))
      (node (ref "CA86") (pin "1") (pinfunction "1_1") (pintype "passive"))
      (node (ref "CA87") (pin "1") (pinfunction "1_1") (pintype "passive"))
      (node (ref "CA87a") (pin "1") (pinfunction "1_1") (pintype "passive"))
      (node (ref "DA15") (pin "2") (pinfunction "2_2") (pintype "passive"))
      (node (ref "QA9") (pin "2") (pinfunction "2_2") (pintype "passive"))
      (node (ref "RA122") (pin "1") (pinfunction "1_1") (pintype "passive"))
      (node (ref "RA124") (pin "1") (pinfunction "1_1") (pintype "passive"))
      (node (ref "RA165") (pin "1") (pinfunction "1_1") (pintype "passive"))
      (node (ref "RA186") (pin "2") (pinfunction "2_2") (pintype "passive"))
      (node (ref "RA215") (pin "2") (pinfunction "2_2") (pintype "passive"))
      (node (ref "UA12") (pin "7") (pinfunction "VCC_7") (pintype "power_in"))
      (node (ref "VCC-AUX") (pin "1") (pinfunction "1_1") (pintype "passive"))
    )
    (net (code "108") (name "VR_DRV") (class "Default")
      (node (ref "CA7") (pin "2") (pinfunction "2_2") (pintype "passive"))
      (node (ref "CNA23") (pin "2") (pinfunction "2_2") (pintype "passive"))
      (node (ref "CNA23") (pin "3") (pinfunction "3_3") (pintype "passive"))
      (node (ref "FA1") (pin "1") (pinfunction "1_1") (pintype "passive"))
    )
    (net (code "109") (name "Vcom") (class "Default")
      (node (ref "CA105") (pin "2") (pinfunction "2_2") (pintype "passive"))
      (node (ref "CA111") (pin "2") (pinfunction "2_2") (pintype "passive"))
      (node (ref "DA17") (pin "1") (pinfunction "A_1") (pintype "passive"))
      (node (ref "QA11") (pin "3") (pinfunction "3_3") (pintype "passive"))
      (node (ref "RA166") (pin "1") (pinfunction "1_1") (pintype "passive"))
      (node (ref "UA12") (pin "1") (pinfunction "COMP_1") (pintype "passive"))
      (node (ref "UA13") (pin "7") (pintype "passive"))
    )
    (net (code "110") (name "Vref-5V") (class "Default")
      (node (ref "CA107") (pin "1") (pinfunction "1_1") (pintype "passive"))
      (node (ref "CA113") (pin "1") (pinfunction "1_1") (pintype "passive"))
      (node (ref "DA16") (pin "2") (pinfunction "2_2") (pintype "passive"))
      (node (ref "QA10") (pin "1") (pinfunction "1_1") (pintype "passive"))
      (node (ref "RA151") (pin "1") (pinfunction "1_1") (pintype "passive"))
      (node (ref "RA161") (pin "2") (pinfunction "2_2") (pintype "passive"))
      (node (ref "RA171") (pin "2") (pinfunction "2_2") (pintype "passive"))
      (node (ref "RA182") (pin "2") (pinfunction "2_2") (pintype "passive"))
      (node (ref "UA12") (pin "8") (pinfunction "VREF_8") (pintype "passive"))
      (node (ref "UA14") (pin "4") (pinfunction "4_4") (pintype "passive"))
      (node (ref "Vref-5V") (pin "1") (pinfunction "1_1") (pintype "passive"))
    )
    (net (code "111") (name "unconnected-(QA5-HS-Pad1)") (class "Default")
      (node (ref "QA5-HS") (pin "1") (pinfunction "1_1") (pintype "passive+no_connect"))
    )
    (net (code "112") (name "unconnected-(QA5-HS-Pad2)") (class "Default")
      (node (ref "QA5-HS") (pin "2") (pinfunction "2_2") (pintype "passive+no_connect"))
    )
    (net (code "113") (name "unconnected-(TA1-Pad6)") (class "Default")
      (node (ref "TA1") (pin "6") (pinfunction "6_6") (pintype "passive+no_connect"))
    )
    (net (code "114") (name "unconnected-(UA10-NC-Pad2)") (class "Default")
      (node (ref "UA10") (pin "2") (pinfunction "NC_2") (pintype "passive+no_connect"))
    )
    (net (code "115") (name "unconnected-(UA10-NC-Pad3)") (class "Default")
      (node (ref "UA10") (pin "3") (pinfunction "NC_3") (pintype "passive+no_connect"))
    )
    (net (code "116") (name "unconnected-(UA11-NC-Pad2)") (class "Default")
      (node (ref "UA11") (pin "2") (pinfunction "NC_2") (pintype "passive+no_connect"))
    )
    (net (code "117") (name "unconnected-(UA11-NC-Pad3)") (class "Default")
      (node (ref "UA11") (pin "3") (pinfunction "NC_3") (pintype "passive+no_connect"))
    )
  )
)
